# Esquematico_LEDS_16x16.net
KiCad netlist of a schematic drawn in Altium Designer
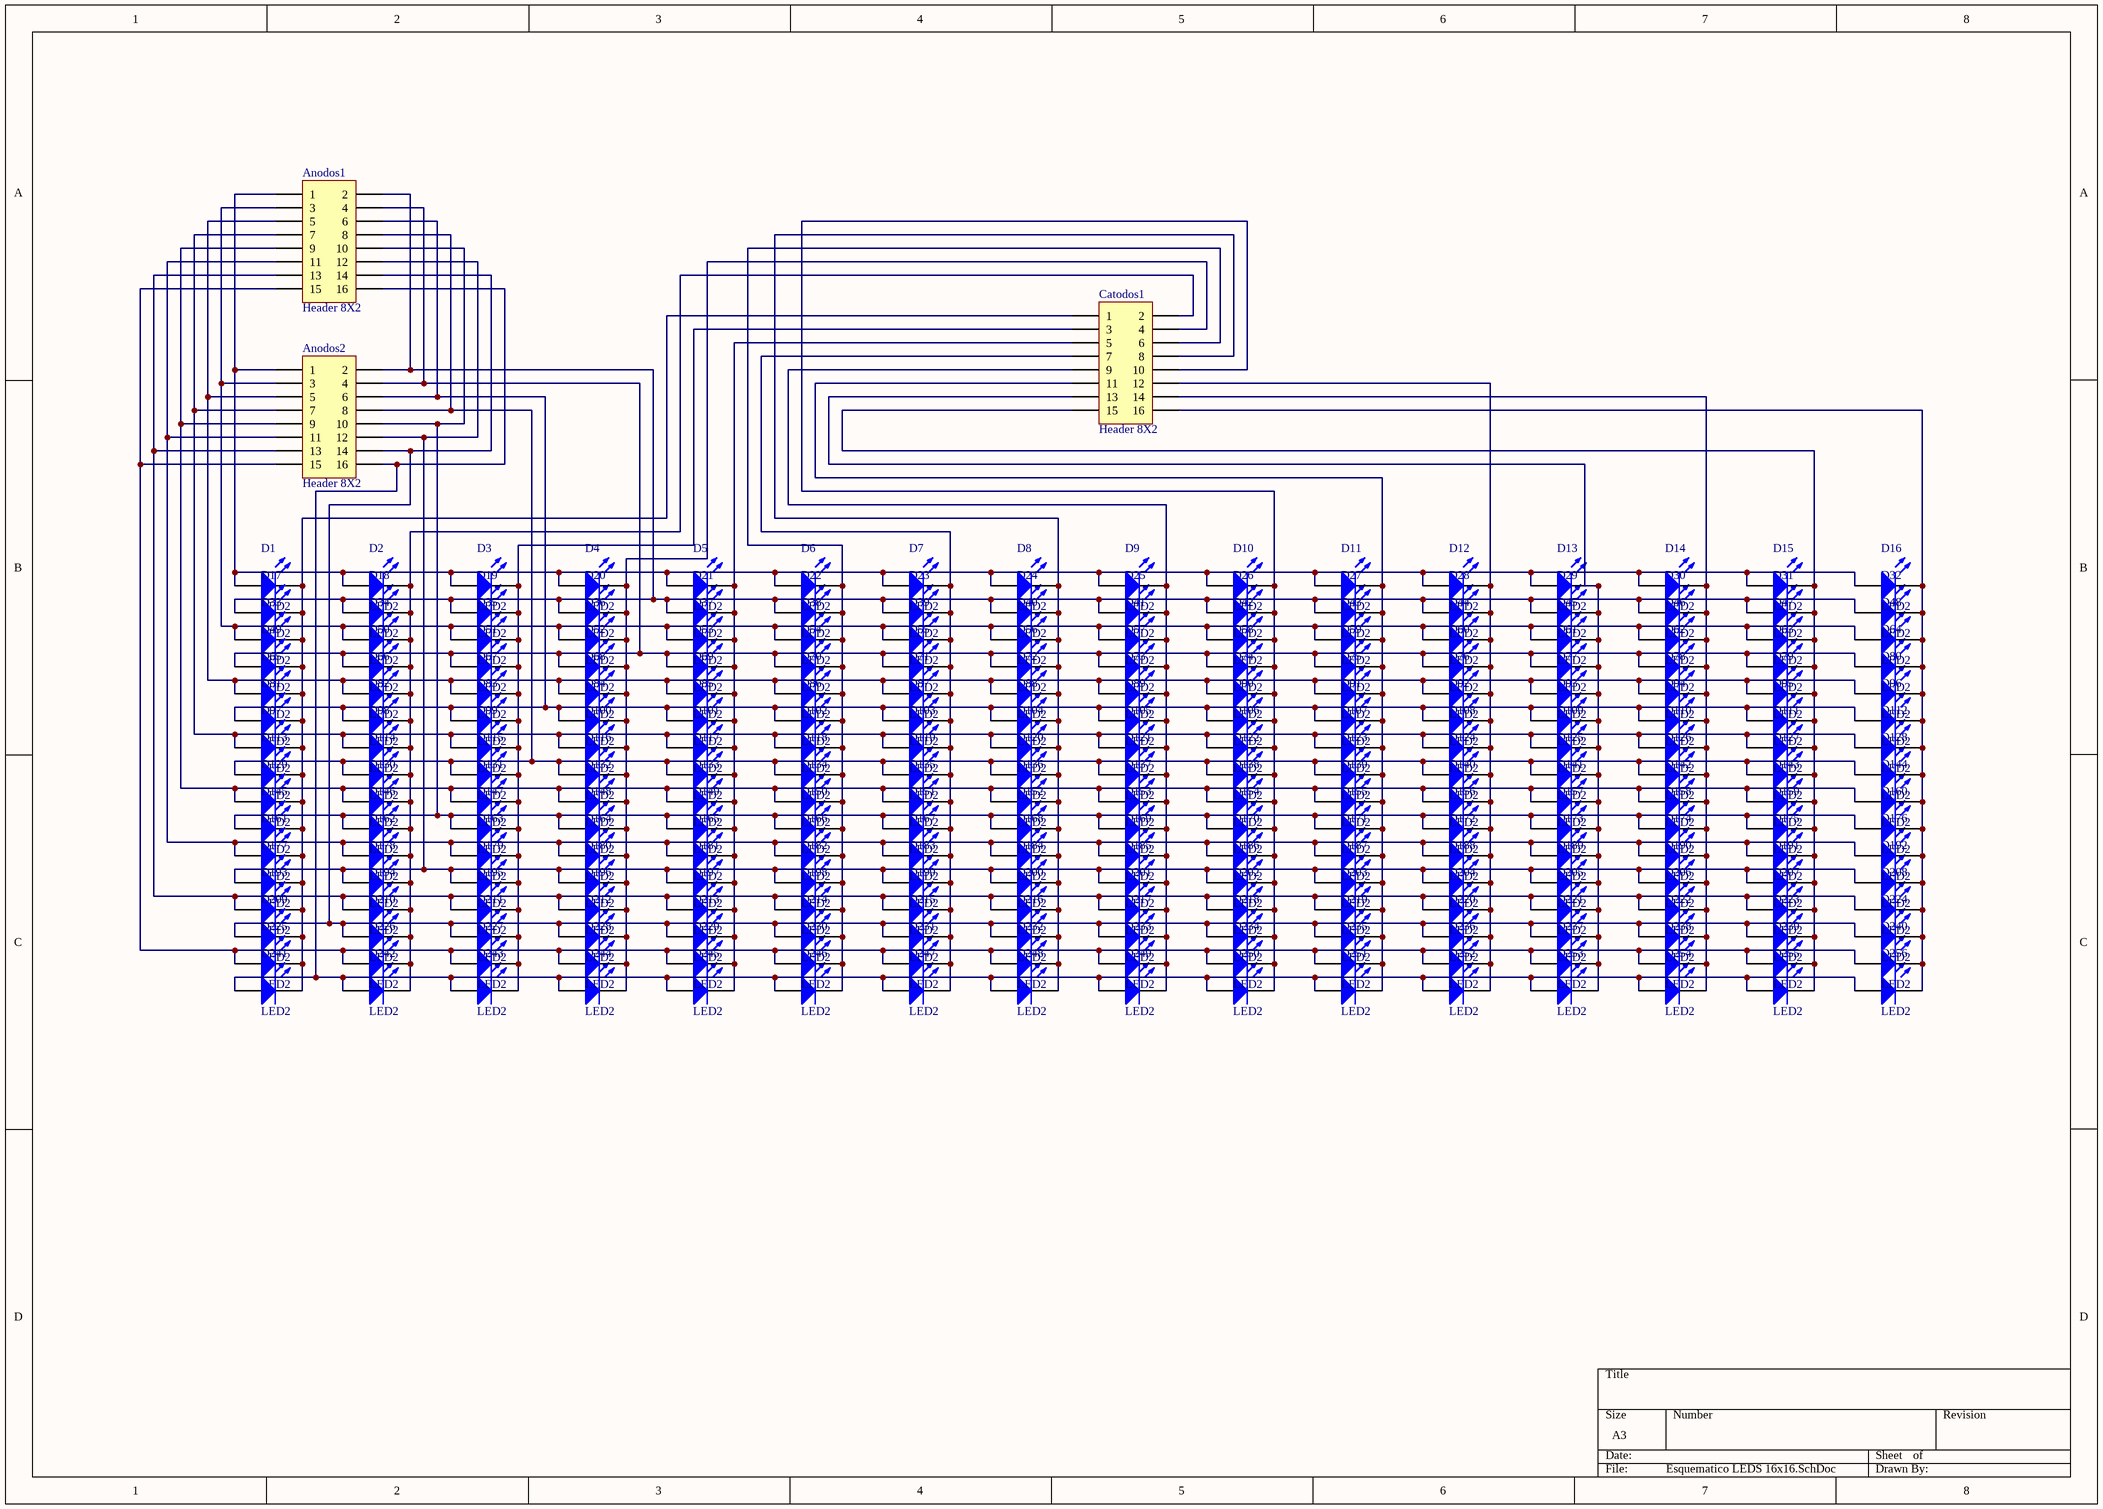
[diagram p0: Esquematico LEDS 16x16.SchDoc]

(export (version "E")
  (design (tool "Eeschema 10.0.6"))
  (components
    (comp (ref "Anodos1")
      (value "Header 8X2")
      (footprint "HDR2X8")
      (description "Header, 8-Pin, Dual row")
      (fields (field (name "PUBLISHER") "Altium Limited"))
      (libsource (lib "Miscellaneous Connectors") (part "Header 8X2"))
    )
    (comp (ref "Anodos2")
      (value "Header 8X2")
      (footprint "HDR2X8")
      (description "Header, 8-Pin, Dual row")
      (fields (field (name "PUBLISHER") "Altium Limited"))
      (libsource (lib "Miscellaneous Connectors") (part "Header 8X2"))
    )
    (comp (ref "Catodos1")
      (value "Header 8X2")
      (footprint "HDR2X8")
      (description "Header, 8-Pin, Dual row")
      (fields (field (name "PUBLISHER") "Altium Limited"))
      (libsource (lib "Miscellaneous Connectors") (part "Header 8X2"))
    )
    (comp (ref "D1")
      (value "LED2")
      (footprint "3.2X1.6X1.1")
      (description "Typical RED, GREEN, YELLOW, AMBER GaAs LED")
      (fields (field (name "PUBLISHER") "Altium Limited"))
      (libsource (lib "Miscellaneous Devices") (part "LED2"))
    )
    (comp (ref "D2")
      (value "LED2")
      (footprint "3.2X1.6X1.1")
      (description "Typical RED, GREEN, YELLOW, AMBER GaAs LED")
      (fields (field (name "PUBLISHER") "Altium Limited"))
      (libsource (lib "Miscellaneous Devices") (part "LED2"))
    )
    (comp (ref "D3")
      (value "LED2")
      (footprint "3.2X1.6X1.1")
      (description "Typical RED, GREEN, YELLOW, AMBER GaAs LED")
      (fields (field (name "PUBLISHER") "Altium Limited"))
      (libsource (lib "Miscellaneous Devices") (part "LED2"))
    )
    (comp (ref "D4")
      (value "LED2")
      (footprint "3.2X1.6X1.1")
      (description "Typical RED, GREEN, YELLOW, AMBER GaAs LED")
      (fields (field (name "PUBLISHER") "Altium Limited"))
      (libsource (lib "Miscellaneous Devices") (part "LED2"))
    )
    (comp (ref "D5")
      (value "LED2")
      (footprint "3.2X1.6X1.1")
      (description "Typical RED, GREEN, YELLOW, AMBER GaAs LED")
      (fields (field (name "PUBLISHER") "Altium Limited"))
      (libsource (lib "Miscellaneous Devices") (part "LED2"))
    )
    (comp (ref "D6")
      (value "LED2")
      (footprint "3.2X1.6X1.1")
      (description "Typical RED, GREEN, YELLOW, AMBER GaAs LED")
      (fields (field (name "PUBLISHER") "Altium Limited"))
      (libsource (lib "Miscellaneous Devices") (part "LED2"))
    )
    (comp (ref "D7")
      (value "LED2")
      (footprint "3.2X1.6X1.1")
      (description "Typical RED, GREEN, YELLOW, AMBER GaAs LED")
      (fields (field (name "PUBLISHER") "Altium Limited"))
      (libsource (lib "Miscellaneous Devices") (part "LED2"))
    )
    (comp (ref "D8")
      (value "LED2")
      (footprint "3.2X1.6X1.1")
      (description "Typical RED, GREEN, YELLOW, AMBER GaAs LED")
      (fields (field (name "PUBLISHER") "Altium Limited"))
      (libsource (lib "Miscellaneous Devices") (part "LED2"))
    )
    (comp (ref "D9")
      (value "LED2")
      (footprint "3.2X1.6X1.1")
      (description "Typical RED, GREEN, YELLOW, AMBER GaAs LED")
      (fields (field (name "PUBLISHER") "Altium Limited"))
      (libsource (lib "Miscellaneous Devices") (part "LED2"))
    )
    (comp (ref "D10")
      (value "LED2")
      (footprint "3.2X1.6X1.1")
      (description "Typical RED, GREEN, YELLOW, AMBER GaAs LED")
      (fields (field (name "PUBLISHER") "Altium Limited"))
      (libsource (lib "Miscellaneous Devices") (part "LED2"))
    )
    (comp (ref "D11")
      (value "LED2")
      (footprint "3.2X1.6X1.1")
      (description "Typical RED, GREEN, YELLOW, AMBER GaAs LED")
      (fields (field (name "PUBLISHER") "Altium Limited"))
      (libsource (lib "Miscellaneous Devices") (part "LED2"))
    )
    (comp (ref "D12")
      (value "LED2")
      (footprint "3.2X1.6X1.1")
      (description "Typical RED, GREEN, YELLOW, AMBER GaAs LED")
      (fields (field (name "PUBLISHER") "Altium Limited"))
      (libsource (lib "Miscellaneous Devices") (part "LED2"))
    )
    (comp (ref "D13")
      (value "LED2")
      (footprint "3.2X1.6X1.1")
      (description "Typical RED, GREEN, YELLOW, AMBER GaAs LED")
      (fields (field (name "PUBLISHER") "Altium Limited"))
      (libsource (lib "Miscellaneous Devices") (part "LED2"))
    )
    (comp (ref "D14")
      (value "LED2")
      (footprint "3.2X1.6X1.1")
      (description "Typical RED, GREEN, YELLOW, AMBER GaAs LED")
      (fields (field (name "PUBLISHER") "Altium Limited"))
      (libsource (lib "Miscellaneous Devices") (part "LED2"))
    )
    (comp (ref "D15")
      (value "LED2")
      (footprint "3.2X1.6X1.1")
      (description "Typical RED, GREEN, YELLOW, AMBER GaAs LED")
      (fields (field (name "PUBLISHER") "Altium Limited"))
      (libsource (lib "Miscellaneous Devices") (part "LED2"))
    )
    (comp (ref "D16")
      (value "LED2")
      (footprint "3.2X1.6X1.1")
      (description "Typical RED, GREEN, YELLOW, AMBER GaAs LED")
      (fields (field (name "PUBLISHER") "Altium Limited"))
      (libsource (lib "Miscellaneous Devices") (part "LED2"))
    )
    (comp (ref "D17")
      (value "LED2")
      (footprint "3.2X1.6X1.1")
      (description "Typical RED, GREEN, YELLOW, AMBER GaAs LED")
      (fields (field (name "PUBLISHER") "Altium Limited"))
      (libsource (lib "Miscellaneous Devices") (part "LED2"))
    )
    (comp (ref "D18")
      (value "LED2")
      (footprint "3.2X1.6X1.1")
      (description "Typical RED, GREEN, YELLOW, AMBER GaAs LED")
      (fields (field (name "PUBLISHER") "Altium Limited"))
      (libsource (lib "Miscellaneous Devices") (part "LED2"))
    )
    (comp (ref "D19")
      (value "LED2")
      (footprint "3.2X1.6X1.1")
      (description "Typical RED, GREEN, YELLOW, AMBER GaAs LED")
      (fields (field (name "PUBLISHER") "Altium Limited"))
      (libsource (lib "Miscellaneous Devices") (part "LED2"))
    )
    (comp (ref "D20")
      (value "LED2")
      (footprint "3.2X1.6X1.1")
      (description "Typical RED, GREEN, YELLOW, AMBER GaAs LED")
      (fields (field (name "PUBLISHER") "Altium Limited"))
      (libsource (lib "Miscellaneous Devices") (part "LED2"))
    )
    (comp (ref "D21")
      (value "LED2")
      (footprint "3.2X1.6X1.1")
      (description "Typical RED, GREEN, YELLOW, AMBER GaAs LED")
      (fields (field (name "PUBLISHER") "Altium Limited"))
      (libsource (lib "Miscellaneous Devices") (part "LED2"))
    )
    (comp (ref "D22")
      (value "LED2")
      (footprint "3.2X1.6X1.1")
      (description "Typical RED, GREEN, YELLOW, AMBER GaAs LED")
      (fields (field (name "PUBLISHER") "Altium Limited"))
      (libsource (lib "Miscellaneous Devices") (part "LED2"))
    )
    (comp (ref "D23")
      (value "LED2")
      (footprint "3.2X1.6X1.1")
      (description "Typical RED, GREEN, YELLOW, AMBER GaAs LED")
      (fields (field (name "PUBLISHER") "Altium Limited"))
      (libsource (lib "Miscellaneous Devices") (part "LED2"))
    )
    (comp (ref "D24")
      (value "LED2")
      (footprint "3.2X1.6X1.1")
      (description "Typical RED, GREEN, YELLOW, AMBER GaAs LED")
      (fields (field (name "PUBLISHER") "Altium Limited"))
      (libsource (lib "Miscellaneous Devices") (part "LED2"))
    )
    (comp (ref "D25")
      (value "LED2")
      (footprint "3.2X1.6X1.1")
      (description "Typical RED, GREEN, YELLOW, AMBER GaAs LED")
      (fields (field (name "PUBLISHER") "Altium Limited"))
      (libsource (lib "Miscellaneous Devices") (part "LED2"))
    )
    (comp (ref "D26")
      (value "LED2")
      (footprint "3.2X1.6X1.1")
      (description "Typical RED, GREEN, YELLOW, AMBER GaAs LED")
      (fields (field (name "PUBLISHER") "Altium Limited"))
      (libsource (lib "Miscellaneous Devices") (part "LED2"))
    )
    (comp (ref "D27")
      (value "LED2")
      (footprint "3.2X1.6X1.1")
      (description "Typical RED, GREEN, YELLOW, AMBER GaAs LED")
      (fields (field (name "PUBLISHER") "Altium Limited"))
      (libsource (lib "Miscellaneous Devices") (part "LED2"))
    )
    (comp (ref "D28")
      (value "LED2")
      (footprint "3.2X1.6X1.1")
      (description "Typical RED, GREEN, YELLOW, AMBER GaAs LED")
      (fields (field (name "PUBLISHER") "Altium Limited"))
      (libsource (lib "Miscellaneous Devices") (part "LED2"))
    )
    (comp (ref "D29")
      (value "LED2")
      (footprint "3.2X1.6X1.1")
      (description "Typical RED, GREEN, YELLOW, AMBER GaAs LED")
      (fields (field (name "PUBLISHER") "Altium Limited"))
      (libsource (lib "Miscellaneous Devices") (part "LED2"))
    )
    (comp (ref "D30")
      (value "LED2")
      (footprint "3.2X1.6X1.1")
      (description "Typical RED, GREEN, YELLOW, AMBER GaAs LED")
      (fields (field (name "PUBLISHER") "Altium Limited"))
      (libsource (lib "Miscellaneous Devices") (part "LED2"))
    )
    (comp (ref "D31")
      (value "LED2")
      (footprint "3.2X1.6X1.1")
      (description "Typical RED, GREEN, YELLOW, AMBER GaAs LED")
      (fields (field (name "PUBLISHER") "Altium Limited"))
      (libsource (lib "Miscellaneous Devices") (part "LED2"))
    )
    (comp (ref "D32")
      (value "LED2")
      (footprint "3.2X1.6X1.1")
      (description "Typical RED, GREEN, YELLOW, AMBER GaAs LED")
      (fields (field (name "PUBLISHER") "Altium Limited"))
      (libsource (lib "Miscellaneous Devices") (part "LED2"))
    )
    (comp (ref "D33")
      (value "LED2")
      (footprint "3.2X1.6X1.1")
      (description "Typical RED, GREEN, YELLOW, AMBER GaAs LED")
      (fields (field (name "PUBLISHER") "Altium Limited"))
      (libsource (lib "Miscellaneous Devices") (part "LED2"))
    )
    (comp (ref "D34")
      (value "LED2")
      (footprint "3.2X1.6X1.1")
      (description "Typical RED, GREEN, YELLOW, AMBER GaAs LED")
      (fields (field (name "PUBLISHER") "Altium Limited"))
      (libsource (lib "Miscellaneous Devices") (part "LED2"))
    )
    (comp (ref "D35")
      (value "LED2")
      (footprint "3.2X1.6X1.1")
      (description "Typical RED, GREEN, YELLOW, AMBER GaAs LED")
      (fields (field (name "PUBLISHER") "Altium Limited"))
      (libsource (lib "Miscellaneous Devices") (part "LED2"))
    )
    (comp (ref "D36")
      (value "LED2")
      (footprint "3.2X1.6X1.1")
      (description "Typical RED, GREEN, YELLOW, AMBER GaAs LED")
      (fields (field (name "PUBLISHER") "Altium Limited"))
      (libsource (lib "Miscellaneous Devices") (part "LED2"))
    )
    (comp (ref "D37")
      (value "LED2")
      (footprint "3.2X1.6X1.1")
      (description "Typical RED, GREEN, YELLOW, AMBER GaAs LED")
      (fields (field (name "PUBLISHER") "Altium Limited"))
      (libsource (lib "Miscellaneous Devices") (part "LED2"))
    )
    (comp (ref "D38")
      (value "LED2")
      (footprint "3.2X1.6X1.1")
      (description "Typical RED, GREEN, YELLOW, AMBER GaAs LED")
      (fields (field (name "PUBLISHER") "Altium Limited"))
      (libsource (lib "Miscellaneous Devices") (part "LED2"))
    )
    (comp (ref "D39")
      (value "LED2")
      (footprint "3.2X1.6X1.1")
      (description "Typical RED, GREEN, YELLOW, AMBER GaAs LED")
      (fields (field (name "PUBLISHER") "Altium Limited"))
      (libsource (lib "Miscellaneous Devices") (part "LED2"))
    )
    (comp (ref "D40")
      (value "LED2")
      (footprint "3.2X1.6X1.1")
      (description "Typical RED, GREEN, YELLOW, AMBER GaAs LED")
      (fields (field (name "PUBLISHER") "Altium Limited"))
      (libsource (lib "Miscellaneous Devices") (part "LED2"))
    )
    (comp (ref "D41")
      (value "LED2")
      (footprint "3.2X1.6X1.1")
      (description "Typical RED, GREEN, YELLOW, AMBER GaAs LED")
      (fields (field (name "PUBLISHER") "Altium Limited"))
      (libsource (lib "Miscellaneous Devices") (part "LED2"))
    )
    (comp (ref "D42")
      (value "LED2")
      (footprint "3.2X1.6X1.1")
      (description "Typical RED, GREEN, YELLOW, AMBER GaAs LED")
      (fields (field (name "PUBLISHER") "Altium Limited"))
      (libsource (lib "Miscellaneous Devices") (part "LED2"))
    )
    (comp (ref "D43")
      (value "LED2")
      (footprint "3.2X1.6X1.1")
      (description "Typical RED, GREEN, YELLOW, AMBER GaAs LED")
      (fields (field (name "PUBLISHER") "Altium Limited"))
      (libsource (lib "Miscellaneous Devices") (part "LED2"))
    )
    (comp (ref "D44")
      (value "LED2")
      (footprint "3.2X1.6X1.1")
      (description "Typical RED, GREEN, YELLOW, AMBER GaAs LED")
      (fields (field (name "PUBLISHER") "Altium Limited"))
      (libsource (lib "Miscellaneous Devices") (part "LED2"))
    )
    (comp (ref "D45")
      (value "LED2")
      (footprint "3.2X1.6X1.1")
      (description "Typical RED, GREEN, YELLOW, AMBER GaAs LED")
      (fields (field (name "PUBLISHER") "Altium Limited"))
      (libsource (lib "Miscellaneous Devices") (part "LED2"))
    )
    (comp (ref "D46")
      (value "LED2")
      (footprint "3.2X1.6X1.1")
      (description "Typical RED, GREEN, YELLOW, AMBER GaAs LED")
      (fields (field (name "PUBLISHER") "Altium Limited"))
      (libsource (lib "Miscellaneous Devices") (part "LED2"))
    )
    (comp (ref "D47")
      (value "LED2")
      (footprint "3.2X1.6X1.1")
      (description "Typical RED, GREEN, YELLOW, AMBER GaAs LED")
      (fields (field (name "PUBLISHER") "Altium Limited"))
      (libsource (lib "Miscellaneous Devices") (part "LED2"))
    )
    (comp (ref "D48")
      (value "LED2")
      (footprint "3.2X1.6X1.1")
      (description "Typical RED, GREEN, YELLOW, AMBER GaAs LED")
      (fields (field (name "PUBLISHER") "Altium Limited"))
      (libsource (lib "Miscellaneous Devices") (part "LED2"))
    )
    (comp (ref "D49")
      (value "LED2")
      (footprint "3.2X1.6X1.1")
      (description "Typical RED, GREEN, YELLOW, AMBER GaAs LED")
      (fields (field (name "PUBLISHER") "Altium Limited"))
      (libsource (lib "Miscellaneous Devices") (part "LED2"))
    )
    (comp (ref "D50")
      (value "LED2")
      (footprint "3.2X1.6X1.1")
      (description "Typical RED, GREEN, YELLOW, AMBER GaAs LED")
      (fields (field (name "PUBLISHER") "Altium Limited"))
      (libsource (lib "Miscellaneous Devices") (part "LED2"))
    )
    (comp (ref "D51")
      (value "LED2")
      (footprint "3.2X1.6X1.1")
      (description "Typical RED, GREEN, YELLOW, AMBER GaAs LED")
      (fields (field (name "PUBLISHER") "Altium Limited"))
      (libsource (lib "Miscellaneous Devices") (part "LED2"))
    )
    (comp (ref "D52")
      (value "LED2")
      (footprint "3.2X1.6X1.1")
      (description "Typical RED, GREEN, YELLOW, AMBER GaAs LED")
      (fields (field (name "PUBLISHER") "Altium Limited"))
      (libsource (lib "Miscellaneous Devices") (part "LED2"))
    )
    (comp (ref "D53")
      (value "LED2")
      (footprint "3.2X1.6X1.1")
      (description "Typical RED, GREEN, YELLOW, AMBER GaAs LED")
      (fields (field (name "PUBLISHER") "Altium Limited"))
      (libsource (lib "Miscellaneous Devices") (part "LED2"))
    )
    (comp (ref "D54")
      (value "LED2")
      (footprint "3.2X1.6X1.1")
      (description "Typical RED, GREEN, YELLOW, AMBER GaAs LED")
      (fields (field (name "PUBLISHER") "Altium Limited"))
      (libsource (lib "Miscellaneous Devices") (part "LED2"))
    )
    (comp (ref "D55")
      (value "LED2")
      (footprint "3.2X1.6X1.1")
      (description "Typical RED, GREEN, YELLOW, AMBER GaAs LED")
      (fields (field (name "PUBLISHER") "Altium Limited"))
      (libsource (lib "Miscellaneous Devices") (part "LED2"))
    )
    (comp (ref "D56")
      (value "LED2")
      (footprint "3.2X1.6X1.1")
      (description "Typical RED, GREEN, YELLOW, AMBER GaAs LED")
      (fields (field (name "PUBLISHER") "Altium Limited"))
      (libsource (lib "Miscellaneous Devices") (part "LED2"))
    )
    (comp (ref "D57")
      (value "LED2")
      (footprint "3.2X1.6X1.1")
      (description "Typical RED, GREEN, YELLOW, AMBER GaAs LED")
      (fields (field (name "PUBLISHER") "Altium Limited"))
      (libsource (lib "Miscellaneous Devices") (part "LED2"))
    )
    (comp (ref "D58")
      (value "LED2")
      (footprint "3.2X1.6X1.1")
      (description "Typical RED, GREEN, YELLOW, AMBER GaAs LED")
      (fields (field (name "PUBLISHER") "Altium Limited"))
      (libsource (lib "Miscellaneous Devices") (part "LED2"))
    )
    (comp (ref "D59")
      (value "LED2")
      (footprint "3.2X1.6X1.1")
      (description "Typical RED, GREEN, YELLOW, AMBER GaAs LED")
      (fields (field (name "PUBLISHER") "Altium Limited"))
      (libsource (lib "Miscellaneous Devices") (part "LED2"))
    )
    (comp (ref "D60")
      (value "LED2")
      (footprint "3.2X1.6X1.1")
      (description "Typical RED, GREEN, YELLOW, AMBER GaAs LED")
      (fields (field (name "PUBLISHER") "Altium Limited"))
      (libsource (lib "Miscellaneous Devices") (part "LED2"))
    )
    (comp (ref "D61")
      (value "LED2")
      (footprint "3.2X1.6X1.1")
      (description "Typical RED, GREEN, YELLOW, AMBER GaAs LED")
      (fields (field (name "PUBLISHER") "Altium Limited"))
      (libsource (lib "Miscellaneous Devices") (part "LED2"))
    )
    (comp (ref "D62")
      (value "LED2")
      (footprint "3.2X1.6X1.1")
      (description "Typical RED, GREEN, YELLOW, AMBER GaAs LED")
      (fields (field (name "PUBLISHER") "Altium Limited"))
      (libsource (lib "Miscellaneous Devices") (part "LED2"))
    )
    (comp (ref "D63")
      (value "LED2")
      (footprint "3.2X1.6X1.1")
      (description "Typical RED, GREEN, YELLOW, AMBER GaAs LED")
      (fields (field (name "PUBLISHER") "Altium Limited"))
      (libsource (lib "Miscellaneous Devices") (part "LED2"))
    )
    (comp (ref "D64")
      (value "LED2")
      (footprint "3.2X1.6X1.1")
      (description "Typical RED, GREEN, YELLOW, AMBER GaAs LED")
      (fields (field (name "PUBLISHER") "Altium Limited"))
      (libsource (lib "Miscellaneous Devices") (part "LED2"))
    )
    (comp (ref "D65")
      (value "LED2")
      (footprint "3.2X1.6X1.1")
      (description "Typical RED, GREEN, YELLOW, AMBER GaAs LED")
      (fields (field (name "PUBLISHER") "Altium Limited"))
      (libsource (lib "Miscellaneous Devices") (part "LED2"))
    )
    (comp (ref "D66")
      (value "LED2")
      (footprint "3.2X1.6X1.1")
      (description "Typical RED, GREEN, YELLOW, AMBER GaAs LED")
      (fields (field (name "PUBLISHER") "Altium Limited"))
      (libsource (lib "Miscellaneous Devices") (part "LED2"))
    )
    (comp (ref "D67")
      (value "LED2")
      (footprint "3.2X1.6X1.1")
      (description "Typical RED, GREEN, YELLOW, AMBER GaAs LED")
      (fields (field (name "PUBLISHER") "Altium Limited"))
      (libsource (lib "Miscellaneous Devices") (part "LED2"))
    )
    (comp (ref "D68")
      (value "LED2")
      (footprint "3.2X1.6X1.1")
      (description "Typical RED, GREEN, YELLOW, AMBER GaAs LED")
      (fields (field (name "PUBLISHER") "Altium Limited"))
      (libsource (lib "Miscellaneous Devices") (part "LED2"))
    )
    (comp (ref "D69")
      (value "LED2")
      (footprint "3.2X1.6X1.1")
      (description "Typical RED, GREEN, YELLOW, AMBER GaAs LED")
      (fields (field (name "PUBLISHER") "Altium Limited"))
      (libsource (lib "Miscellaneous Devices") (part "LED2"))
    )
    (comp (ref "D70")
      (value "LED2")
      (footprint "3.2X1.6X1.1")
      (description "Typical RED, GREEN, YELLOW, AMBER GaAs LED")
      (fields (field (name "PUBLISHER") "Altium Limited"))
      (libsource (lib "Miscellaneous Devices") (part "LED2"))
    )
    (comp (ref "D71")
      (value "LED2")
      (footprint "3.2X1.6X1.1")
      (description "Typical RED, GREEN, YELLOW, AMBER GaAs LED")
      (fields (field (name "PUBLISHER") "Altium Limited"))
      (libsource (lib "Miscellaneous Devices") (part "LED2"))
    )
    (comp (ref "D72")
      (value "LED2")
      (footprint "3.2X1.6X1.1")
      (description "Typical RED, GREEN, YELLOW, AMBER GaAs LED")
      (fields (field (name "PUBLISHER") "Altium Limited"))
      (libsource (lib "Miscellaneous Devices") (part "LED2"))
    )
    (comp (ref "D73")
      (value "LED2")
      (footprint "3.2X1.6X1.1")
      (description "Typical RED, GREEN, YELLOW, AMBER GaAs LED")
      (fields (field (name "PUBLISHER") "Altium Limited"))
      (libsource (lib "Miscellaneous Devices") (part "LED2"))
    )
    (comp (ref "D74")
      (value "LED2")
      (footprint "3.2X1.6X1.1")
      (description "Typical RED, GREEN, YELLOW, AMBER GaAs LED")
      (fields (field (name "PUBLISHER") "Altium Limited"))
      (libsource (lib "Miscellaneous Devices") (part "LED2"))
    )
    (comp (ref "D75")
      (value "LED2")
      (footprint "3.2X1.6X1.1")
      (description "Typical RED, GREEN, YELLOW, AMBER GaAs LED")
      (fields (field (name "PUBLISHER") "Altium Limited"))
      (libsource (lib "Miscellaneous Devices") (part "LED2"))
    )
    (comp (ref "D76")
      (value "LED2")
      (footprint "3.2X1.6X1.1")
      (description "Typical RED, GREEN, YELLOW, AMBER GaAs LED")
      (fields (field (name "PUBLISHER") "Altium Limited"))
      (libsource (lib "Miscellaneous Devices") (part "LED2"))
    )
    (comp (ref "D77")
      (value "LED2")
      (footprint "3.2X1.6X1.1")
      (description "Typical RED, GREEN, YELLOW, AMBER GaAs LED")
      (fields (field (name "PUBLISHER") "Altium Limited"))
      (libsource (lib "Miscellaneous Devices") (part "LED2"))
    )
    (comp (ref "D78")
      (value "LED2")
      (footprint "3.2X1.6X1.1")
      (description "Typical RED, GREEN, YELLOW, AMBER GaAs LED")
      (fields (field (name "PUBLISHER") "Altium Limited"))
      (libsource (lib "Miscellaneous Devices") (part "LED2"))
    )
    (comp (ref "D79")
      (value "LED2")
      (footprint "3.2X1.6X1.1")
      (description "Typical RED, GREEN, YELLOW, AMBER GaAs LED")
      (fields (field (name "PUBLISHER") "Altium Limited"))
      (libsource (lib "Miscellaneous Devices") (part "LED2"))
    )
    (comp (ref "D80")
      (value "LED2")
      (footprint "3.2X1.6X1.1")
      (description "Typical RED, GREEN, YELLOW, AMBER GaAs LED")
      (fields (field (name "PUBLISHER") "Altium Limited"))
      (libsource (lib "Miscellaneous Devices") (part "LED2"))
    )
    (comp (ref "D81")
      (value "LED2")
      (footprint "3.2X1.6X1.1")
      (description "Typical RED, GREEN, YELLOW, AMBER GaAs LED")
      (fields (field (name "PUBLISHER") "Altium Limited"))
      (libsource (lib "Miscellaneous Devices") (part "LED2"))
    )
    (comp (ref "D82")
      (value "LED2")
      (footprint "3.2X1.6X1.1")
      (description "Typical RED, GREEN, YELLOW, AMBER GaAs LED")
      (fields (field (name "PUBLISHER") "Altium Limited"))
      (libsource (lib "Miscellaneous Devices") (part "LED2"))
    )
    (comp (ref "D83")
      (value "LED2")
      (footprint "3.2X1.6X1.1")
      (description "Typical RED, GREEN, YELLOW, AMBER GaAs LED")
      (fields (field (name "PUBLISHER") "Altium Limited"))
      (libsource (lib "Miscellaneous Devices") (part "LED2"))
    )
    (comp (ref "D84")
      (value "LED2")
      (footprint "3.2X1.6X1.1")
      (description "Typical RED, GREEN, YELLOW, AMBER GaAs LED")
      (fields (field (name "PUBLISHER") "Altium Limited"))
      (libsource (lib "Miscellaneous Devices") (part "LED2"))
    )
    (comp (ref "D85")
      (value "LED2")
      (footprint "3.2X1.6X1.1")
      (description "Typical RED, GREEN, YELLOW, AMBER GaAs LED")
      (fields (field (name "PUBLISHER") "Altium Limited"))
      (libsource (lib "Miscellaneous Devices") (part "LED2"))
    )
    (comp (ref "D86")
      (value "LED2")
      (footprint "3.2X1.6X1.1")
      (description "Typical RED, GREEN, YELLOW, AMBER GaAs LED")
      (fields (field (name "PUBLISHER") "Altium Limited"))
      (libsource (lib "Miscellaneous Devices") (part "LED2"))
    )
    (comp (ref "D87")
      (value "LED2")
      (footprint "3.2X1.6X1.1")
      (description "Typical RED, GREEN, YELLOW, AMBER GaAs LED")
      (fields (field (name "PUBLISHER") "Altium Limited"))
      (libsource (lib "Miscellaneous Devices") (part "LED2"))
    )
    (comp (ref "D88")
      (value "LED2")
      (footprint "3.2X1.6X1.1")
      (description "Typical RED, GREEN, YELLOW, AMBER GaAs LED")
      (fields (field (name "PUBLISHER") "Altium Limited"))
      (libsource (lib "Miscellaneous Devices") (part "LED2"))
    )
    (comp (ref "D89")
      (value "LED2")
      (footprint "3.2X1.6X1.1")
      (description "Typical RED, GREEN, YELLOW, AMBER GaAs LED")
      (fields (field (name "PUBLISHER") "Altium Limited"))
      (libsource (lib "Miscellaneous Devices") (part "LED2"))
    )
    (comp (ref "D90")
      (value "LED2")
      (footprint "3.2X1.6X1.1")
      (description "Typical RED, GREEN, YELLOW, AMBER GaAs LED")
      (fields (field (name "PUBLISHER") "Altium Limited"))
      (libsource (lib "Miscellaneous Devices") (part "LED2"))
    )
    (comp (ref "D91")
      (value "LED2")
      (footprint "3.2X1.6X1.1")
      (description "Typical RED, GREEN, YELLOW, AMBER GaAs LED")
      (fields (field (name "PUBLISHER") "Altium Limited"))
      (libsource (lib "Miscellaneous Devices") (part "LED2"))
    )
    (comp (ref "D92")
      (value "LED2")
      (footprint "3.2X1.6X1.1")
      (description "Typical RED, GREEN, YELLOW, AMBER GaAs LED")
      (fields (field (name "PUBLISHER") "Altium Limited"))
      (libsource (lib "Miscellaneous Devices") (part "LED2"))
    )
    (comp (ref "D93")
      (value "LED2")
      (footprint "3.2X1.6X1.1")
      (description "Typical RED, GREEN, YELLOW, AMBER GaAs LED")
      (fields (field (name "PUBLISHER") "Altium Limited"))
      (libsource (lib "Miscellaneous Devices") (part "LED2"))
    )
    (comp (ref "D94")
      (value "LED2")
      (footprint "3.2X1.6X1.1")
      (description "Typical RED, GREEN, YELLOW, AMBER GaAs LED")
      (fields (field (name "PUBLISHER") "Altium Limited"))
      (libsource (lib "Miscellaneous Devices") (part "LED2"))
    )
    (comp (ref "D95")
      (value "LED2")
      (footprint "3.2X1.6X1.1")
      (description "Typical RED, GREEN, YELLOW, AMBER GaAs LED")
      (fields (field (name "PUBLISHER") "Altium Limited"))
      (libsource (lib "Miscellaneous Devices") (part "LED2"))
    )
    (comp (ref "D96")
      (value "LED2")
      (footprint "3.2X1.6X1.1")
      (description "Typical RED, GREEN, YELLOW, AMBER GaAs LED")
      (fields (field (name "PUBLISHER") "Altium Limited"))
      (libsource (lib "Miscellaneous Devices") (part "LED2"))
    )
    (comp (ref "D97")
      (value "LED2")
      (footprint "3.2X1.6X1.1")
      (description "Typical RED, GREEN, YELLOW, AMBER GaAs LED")
      (fields (field (name "PUBLISHER") "Altium Limited"))
      (libsource (lib "Miscellaneous Devices") (part "LED2"))
    )
    (comp (ref "D98")
      (value "LED2")
      (footprint "3.2X1.6X1.1")
      (description "Typical RED, GREEN, YELLOW, AMBER GaAs LED")
      (fields (field (name "PUBLISHER") "Altium Limited"))
      (libsource (lib "Miscellaneous Devices") (part "LED2"))
    )
    (comp (ref "D99")
      (value "LED2")
      (footprint "3.2X1.6X1.1")
      (description "Typical RED, GREEN, YELLOW, AMBER GaAs LED")
      (fields (field (name "PUBLISHER") "Altium Limited"))
      (libsource (lib "Miscellaneous Devices") (part "LED2"))
    )
    (comp (ref "D100")
      (value "LED2")
      (footprint "3.2X1.6X1.1")
      (description "Typical RED, GREEN, YELLOW, AMBER GaAs LED")
      (fields (field (name "PUBLISHER") "Altium Limited"))
      (libsource (lib "Miscellaneous Devices") (part "LED2"))
    )
    (comp (ref "D101")
      (value "LED2")
      (footprint "3.2X1.6X1.1")
      (description "Typical RED, GREEN, YELLOW, AMBER GaAs LED")
      (fields (field (name "PUBLISHER") "Altium Limited"))
      (libsource (lib "Miscellaneous Devices") (part "LED2"))
    )
    (comp (ref "D102")
      (value "LED2")
      (footprint "3.2X1.6X1.1")
      (description "Typical RED, GREEN, YELLOW, AMBER GaAs LED")
      (fields (field (name "PUBLISHER") "Altium Limited"))
      (libsource (lib "Miscellaneous Devices") (part "LED2"))
    )
    (comp (ref "D103")
      (value "LED2")
      (footprint "3.2X1.6X1.1")
      (description "Typical RED, GREEN, YELLOW, AMBER GaAs LED")
      (fields (field (name "PUBLISHER") "Altium Limited"))
      (libsource (lib "Miscellaneous Devices") (part "LED2"))
    )
    (comp (ref "D104")
      (value "LED2")
      (footprint "3.2X1.6X1.1")
      (description "Typical RED, GREEN, YELLOW, AMBER GaAs LED")
      (fields (field (name "PUBLISHER") "Altium Limited"))
      (libsource (lib "Miscellaneous Devices") (part "LED2"))
    )
    (comp (ref "D105")
      (value "LED2")
      (footprint "3.2X1.6X1.1")
      (description "Typical RED, GREEN, YELLOW, AMBER GaAs LED")
      (fields (field (name "PUBLISHER") "Altium Limited"))
      (libsource (lib "Miscellaneous Devices") (part "LED2"))
    )
    (comp (ref "D106")
      (value "LED2")
      (footprint "3.2X1.6X1.1")
      (description "Typical RED, GREEN, YELLOW, AMBER GaAs LED")
      (fields (field (name "PUBLISHER") "Altium Limited"))
      (libsource (lib "Miscellaneous Devices") (part "LED2"))
    )
    (comp (ref "D107")
      (value "LED2")
      (footprint "3.2X1.6X1.1")
      (description "Typical RED, GREEN, YELLOW, AMBER GaAs LED")
      (fields (field (name "PUBLISHER") "Altium Limited"))
      (libsource (lib "Miscellaneous Devices") (part "LED2"))
    )
    (comp (ref "D108")
      (value "LED2")
      (footprint "3.2X1.6X1.1")
      (description "Typical RED, GREEN, YELLOW, AMBER GaAs LED")
      (fields (field (name "PUBLISHER") "Altium Limited"))
      (libsource (lib "Miscellaneous Devices") (part "LED2"))
    )
    (comp (ref "D109")
      (value "LED2")
      (footprint "3.2X1.6X1.1")
      (description "Typical RED, GREEN, YELLOW, AMBER GaAs LED")
      (fields (field (name "PUBLISHER") "Altium Limited"))
      (libsource (lib "Miscellaneous Devices") (part "LED2"))
    )
    (comp (ref "D110")
      (value "LED2")
      (footprint "3.2X1.6X1.1")
      (description "Typical RED, GREEN, YELLOW, AMBER GaAs LED")
      (fields (field (name "PUBLISHER") "Altium Limited"))
      (libsource (lib "Miscellaneous Devices") (part "LED2"))
    )
    (comp (ref "D111")
      (value "LED2")
      (footprint "3.2X1.6X1.1")
      (description "Typical RED, GREEN, YELLOW, AMBER GaAs LED")
      (fields (field (name "PUBLISHER") "Altium Limited"))
      (libsource (lib "Miscellaneous Devices") (part "LED2"))
    )
    (comp (ref "D112")
      (value "LED2")
      (footprint "3.2X1.6X1.1")
      (description "Typical RED, GREEN, YELLOW, AMBER GaAs LED")
      (fields (field (name "PUBLISHER") "Altium Limited"))
      (libsource (lib "Miscellaneous Devices") (part "LED2"))
    )
    (comp (ref "D113")
      (value "LED2")
      (footprint "3.2X1.6X1.1")
      (description "Typical RED, GREEN, YELLOW, AMBER GaAs LED")
      (fields (field (name "PUBLISHER") "Altium Limited"))
      (libsource (lib "Miscellaneous Devices") (part "LED2"))
    )
    (comp (ref "D114")
      (value "LED2")
      (footprint "3.2X1.6X1.1")
      (description "Typical RED, GREEN, YELLOW, AMBER GaAs LED")
      (fields (field (name "PUBLISHER") "Altium Limited"))
      (libsource (lib "Miscellaneous Devices") (part "LED2"))
    )
    (comp (ref "D115")
      (value "LED2")
      (footprint "3.2X1.6X1.1")
      (description "Typical RED, GREEN, YELLOW, AMBER GaAs LED")
      (fields (field (name "PUBLISHER") "Altium Limited"))
      (libsource (lib "Miscellaneous Devices") (part "LED2"))
    )
    (comp (ref "D116")
      (value "LED2")
      (footprint "3.2X1.6X1.1")
      (description "Typical RED, GREEN, YELLOW, AMBER GaAs LED")
      (fields (field (name "PUBLISHER") "Altium Limited"))
      (libsource (lib "Miscellaneous Devices") (part "LED2"))
    )
    (comp (ref "D117")
      (value "LED2")
      (footprint "3.2X1.6X1.1")
      (description "Typical RED, GREEN, YELLOW, AMBER GaAs LED")
      (fields (field (name "PUBLISHER") "Altium Limited"))
      (libsource (lib "Miscellaneous Devices") (part "LED2"))
    )
    (comp (ref "D118")
      (value "LED2")
      (footprint "3.2X1.6X1.1")
      (description "Typical RED, GREEN, YELLOW, AMBER GaAs LED")
      (fields (field (name "PUBLISHER") "Altium Limited"))
      (libsource (lib "Miscellaneous Devices") (part "LED2"))
    )
    (comp (ref "D119")
      (value "LED2")
      (footprint "3.2X1.6X1.1")
      (description "Typical RED, GREEN, YELLOW, AMBER GaAs LED")
      (fields (field (name "PUBLISHER") "Altium Limited"))
      (libsource (lib "Miscellaneous Devices") (part "LED2"))
    )
    (comp (ref "D120")
      (value "LED2")
      (footprint "3.2X1.6X1.1")
      (description "Typical RED, GREEN, YELLOW, AMBER GaAs LED")
      (fields (field (name "PUBLISHER") "Altium Limited"))
      (libsource (lib "Miscellaneous Devices") (part "LED2"))
    )
    (comp (ref "D121")
      (value "LED2")
      (footprint "3.2X1.6X1.1")
      (description "Typical RED, GREEN, YELLOW, AMBER GaAs LED")
      (fields (field (name "PUBLISHER") "Altium Limited"))
      (libsource (lib "Miscellaneous Devices") (part "LED2"))
    )
    (comp (ref "D122")
      (value "LED2")
      (footprint "3.2X1.6X1.1")
      (description "Typical RED, GREEN, YELLOW, AMBER GaAs LED")
      (fields (field (name "PUBLISHER") "Altium Limited"))
      (libsource (lib "Miscellaneous Devices") (part "LED2"))
    )
    (comp (ref "D123")
      (value "LED2")
      (footprint "3.2X1.6X1.1")
      (description "Typical RED, GREEN, YELLOW, AMBER GaAs LED")
      (fields (field (name "PUBLISHER") "Altium Limited"))
      (libsource (lib "Miscellaneous Devices") (part "LED2"))
    )
    (comp (ref "D124")
      (value "LED2")
      (footprint "3.2X1.6X1.1")
      (description "Typical RED, GREEN, YELLOW, AMBER GaAs LED")
      (fields (field (name "PUBLISHER") "Altium Limited"))
      (libsource (lib "Miscellaneous Devices") (part "LED2"))
    )
    (comp (ref "D125")
      (value "LED2")
      (footprint "3.2X1.6X1.1")
      (description "Typical RED, GREEN, YELLOW, AMBER GaAs LED")
      (fields (field (name "PUBLISHER") "Altium Limited"))
      (libsource (lib "Miscellaneous Devices") (part "LED2"))
    )
    (comp (ref "D126")
      (value "LED2")
      (footprint "3.2X1.6X1.1")
      (description "Typical RED, GREEN, YELLOW, AMBER GaAs LED")
      (fields (field (name "PUBLISHER") "Altium Limited"))
      (libsource (lib "Miscellaneous Devices") (part "LED2"))
    )
    (comp (ref "D127")
      (value "LED2")
      (footprint "3.2X1.6X1.1")
      (description "Typical RED, GREEN, YELLOW, AMBER GaAs LED")
      (fields (field (name "PUBLISHER") "Altium Limited"))
      (libsource (lib "Miscellaneous Devices") (part "LED2"))
    )
    (comp (ref "D128")
      (value "LED2")
      (footprint "3.2X1.6X1.1")
      (description "Typical RED, GREEN, YELLOW, AMBER GaAs LED")
      (fields (field (name "PUBLISHER") "Altium Limited"))
      (libsource (lib "Miscellaneous Devices") (part "LED2"))
    )
    (comp (ref "D129")
      (value "LED2")
      (footprint "3.2X1.6X1.1")
      (description "Typical RED, GREEN, YELLOW, AMBER GaAs LED")
      (fields (field (name "PUBLISHER") "Altium Limited"))
      (libsource (lib "Miscellaneous Devices") (part "LED2"))
    )
    (comp (ref "D130")
      (value "LED2")
      (footprint "3.2X1.6X1.1")
      (description "Typical RED, GREEN, YELLOW, AMBER GaAs LED")
      (fields (field (name "PUBLISHER") "Altium Limited"))
      (libsource (lib "Miscellaneous Devices") (part "LED2"))
    )
    (comp (ref "D131")
      (value "LED2")
      (footprint "3.2X1.6X1.1")
      (description "Typical RED, GREEN, YELLOW, AMBER GaAs LED")
      (fields (field (name "PUBLISHER") "Altium Limited"))
      (libsource (lib "Miscellaneous Devices") (part "LED2"))
    )
    (comp (ref "D132")
      (value "LED2")
      (footprint "3.2X1.6X1.1")
      (description "Typical RED, GREEN, YELLOW, AMBER GaAs LED")
      (fields (field (name "PUBLISHER") "Altium Limited"))
      (libsource (lib "Miscellaneous Devices") (part "LED2"))
    )
    (comp (ref "D133")
      (value "LED2")
      (footprint "3.2X1.6X1.1")
      (description "Typical RED, GREEN, YELLOW, AMBER GaAs LED")
      (fields (field (name "PUBLISHER") "Altium Limited"))
      (libsource (lib "Miscellaneous Devices") (part "LED2"))
    )
    (comp (ref "D134")
      (value "LED2")
      (footprint "3.2X1.6X1.1")
      (description "Typical RED, GREEN, YELLOW, AMBER GaAs LED")
      (fields (field (name "PUBLISHER") "Altium Limited"))
      (libsource (lib "Miscellaneous Devices") (part "LED2"))
    )
    (comp (ref "D135")
      (value "LED2")
      (footprint "3.2X1.6X1.1")
      (description "Typical RED, GREEN, YELLOW, AMBER GaAs LED")
      (fields (field (name "PUBLISHER") "Altium Limited"))
      (libsource (lib "Miscellaneous Devices") (part "LED2"))
    )
    (comp (ref "D136")
      (value "LED2")
      (footprint "3.2X1.6X1.1")
      (description "Typical RED, GREEN, YELLOW, AMBER GaAs LED")
      (fields (field (name "PUBLISHER") "Altium Limited"))
      (libsource (lib "Miscellaneous Devices") (part "LED2"))
    )
    (comp (ref "D137")
      (value "LED2")
      (footprint "3.2X1.6X1.1")
      (description "Typical RED, GREEN, YELLOW, AMBER GaAs LED")
      (fields (field (name "PUBLISHER") "Altium Limited"))
      (libsource (lib "Miscellaneous Devices") (part "LED2"))
    )
    (comp (ref "D138")
      (value "LED2")
      (footprint "3.2X1.6X1.1")
      (description "Typical RED, GREEN, YELLOW, AMBER GaAs LED")
      (fields (field (name "PUBLISHER") "Altium Limited"))
      (libsource (lib "Miscellaneous Devices") (part "LED2"))
    )
    (comp (ref "D139")
      (value "LED2")
      (footprint "3.2X1.6X1.1")
      (description "Typical RED, GREEN, YELLOW, AMBER GaAs LED")
      (fields (field (name "PUBLISHER") "Altium Limited"))
      (libsource (lib "Miscellaneous Devices") (part "LED2"))
    )
    (comp (ref "D140")
      (value "LED2")
      (footprint "3.2X1.6X1.1")
      (description "Typical RED, GREEN, YELLOW, AMBER GaAs LED")
      (fields (field (name "PUBLISHER") "Altium Limited"))
      (libsource (lib "Miscellaneous Devices") (part "LED2"))
    )
    (comp (ref "D141")
      (value "LED2")
      (footprint "3.2X1.6X1.1")
      (description "Typical RED, GREEN, YELLOW, AMBER GaAs LED")
      (fields (field (name "PUBLISHER") "Altium Limited"))
      (libsource (lib "Miscellaneous Devices") (part "LED2"))
    )
    (comp (ref "D142")
      (value "LED2")
      (footprint "3.2X1.6X1.1")
      (description "Typical RED, GREEN, YELLOW, AMBER GaAs LED")
      (fields (field (name "PUBLISHER") "Altium Limited"))
      (libsource (lib "Miscellaneous Devices") (part "LED2"))
    )
    (comp (ref "D143")
      (value "LED2")
      (footprint "3.2X1.6X1.1")
      (description "Typical RED, GREEN, YELLOW, AMBER GaAs LED")
      (fields (field (name "PUBLISHER") "Altium Limited"))
      (libsource (lib "Miscellaneous Devices") (part "LED2"))
    )
    (comp (ref "D144")
      (value "LED2")
      (footprint "3.2X1.6X1.1")
      (description "Typical RED, GREEN, YELLOW, AMBER GaAs LED")
      (fields (field (name "PUBLISHER") "Altium Limited"))
      (libsource (lib "Miscellaneous Devices") (part "LED2"))
    )
    (comp (ref "D145")
      (value "LED2")
      (footprint "3.2X1.6X1.1")
      (description "Typical RED, GREEN, YELLOW, AMBER GaAs LED")
      (fields (field (name "PUBLISHER") "Altium Limited"))
      (libsource (lib "Miscellaneous Devices") (part "LED2"))
    )
    (comp (ref "D146")
      (value "LED2")
      (footprint "3.2X1.6X1.1")
      (description "Typical RED, GREEN, YELLOW, AMBER GaAs LED")
      (fields (field (name "PUBLISHER") "Altium Limited"))
      (libsource (lib "Miscellaneous Devices") (part "LED2"))
    )
    (comp (ref "D147")
      (value "LED2")
      (footprint "3.2X1.6X1.1")
      (description "Typical RED, GREEN, YELLOW, AMBER GaAs LED")
      (fields (field (name "PUBLISHER") "Altium Limited"))
      (libsource (lib "Miscellaneous Devices") (part "LED2"))
    )
    (comp (ref "D148")
      (value "LED2")
      (footprint "3.2X1.6X1.1")
      (description "Typical RED, GREEN, YELLOW, AMBER GaAs LED")
      (fields (field (name "PUBLISHER") "Altium Limited"))
      (libsource (lib "Miscellaneous Devices") (part "LED2"))
    )
    (comp (ref "D149")
      (value "LED2")
      (footprint "3.2X1.6X1.1")
      (description "Typical RED, GREEN, YELLOW, AMBER GaAs LED")
      (fields (field (name "PUBLISHER") "Altium Limited"))
      (libsource (lib "Miscellaneous Devices") (part "LED2"))
    )
    (comp (ref "D150")
      (value "LED2")
      (footprint "3.2X1.6X1.1")
      (description "Typical RED, GREEN, YELLOW, AMBER GaAs LED")
      (fields (field (name "PUBLISHER") "Altium Limited"))
      (libsource (lib "Miscellaneous Devices") (part "LED2"))
    )
    (comp (ref "D151")
      (value "LED2")
      (footprint "3.2X1.6X1.1")
      (description "Typical RED, GREEN, YELLOW, AMBER GaAs LED")
      (fields (field (name "PUBLISHER") "Altium Limited"))
      (libsource (lib "Miscellaneous Devices") (part "LED2"))
    )
    (comp (ref "D152")
      (value "LED2")
      (footprint "3.2X1.6X1.1")
      (description "Typical RED, GREEN, YELLOW, AMBER GaAs LED")
      (fields (field (name "PUBLISHER") "Altium Limited"))
      (libsource (lib "Miscellaneous Devices") (part "LED2"))
    )
    (comp (ref "D153")
      (value "LED2")
      (footprint "3.2X1.6X1.1")
      (description "Typical RED, GREEN, YELLOW, AMBER GaAs LED")
      (fields (field (name "PUBLISHER") "Altium Limited"))
      (libsource (lib "Miscellaneous Devices") (part "LED2"))
    )
    (comp (ref "D154")
      (value "LED2")
      (footprint "3.2X1.6X1.1")
      (description "Typical RED, GREEN, YELLOW, AMBER GaAs LED")
      (fields (field (name "PUBLISHER") "Altium Limited"))
      (libsource (lib "Miscellaneous Devices") (part "LED2"))
    )
    (comp (ref "D155")
      (value "LED2")
      (footprint "3.2X1.6X1.1")
      (description "Typical RED, GREEN, YELLOW, AMBER GaAs LED")
      (fields (field (name "PUBLISHER") "Altium Limited"))
      (libsource (lib "Miscellaneous Devices") (part "LED2"))
    )
    (comp (ref "D156")
      (value "LED2")
      (footprint "3.2X1.6X1.1")
      (description "Typical RED, GREEN, YELLOW, AMBER GaAs LED")
      (fields (field (name "PUBLISHER") "Altium Limited"))
      (libsource (lib "Miscellaneous Devices") (part "LED2"))
    )
    (comp (ref "D157")
      (value "LED2")
      (footprint "3.2X1.6X1.1")
      (description "Typical RED, GREEN, YELLOW, AMBER GaAs LED")
      (fields (field (name "PUBLISHER") "Altium Limited"))
      (libsource (lib "Miscellaneous Devices") (part "LED2"))
    )
    (comp (ref "D158")
      (value "LED2")
      (footprint "3.2X1.6X1.1")
      (description "Typical RED, GREEN, YELLOW, AMBER GaAs LED")
      (fields (field (name "PUBLISHER") "Altium Limited"))
      (libsource (lib "Miscellaneous Devices") (part "LED2"))
    )
    (comp (ref "D159")
      (value "LED2")
      (footprint "3.2X1.6X1.1")
      (description "Typical RED, GREEN, YELLOW, AMBER GaAs LED")
      (fields (field (name "PUBLISHER") "Altium Limited"))
      (libsource (lib "Miscellaneous Devices") (part "LED2"))
    )
    (comp (ref "D160")
      (value "LED2")
      (footprint "3.2X1.6X1.1")
      (description "Typical RED, GREEN, YELLOW, AMBER GaAs LED")
      (fields (field (name "PUBLISHER") "Altium Limited"))
      (libsource (lib "Miscellaneous Devices") (part "LED2"))
    )
    (comp (ref "D161")
      (value "LED2")
      (footprint "3.2X1.6X1.1")
      (description "Typical RED, GREEN, YELLOW, AMBER GaAs LED")
      (fields (field (name "PUBLISHER") "Altium Limited"))
      (libsource (lib "Miscellaneous Devices") (part "LED2"))
    )
    (comp (ref "D162")
      (value "LED2")
      (footprint "3.2X1.6X1.1")
      (description "Typical RED, GREEN, YELLOW, AMBER GaAs LED")
      (fields (field (name "PUBLISHER") "Altium Limited"))
      (libsource (lib "Miscellaneous Devices") (part "LED2"))
    )
    (comp (ref "D163")
      (value "LED2")
      (footprint "3.2X1.6X1.1")
      (description "Typical RED, GREEN, YELLOW, AMBER GaAs LED")
      (fields (field (name "PUBLISHER") "Altium Limited"))
      (libsource (lib "Miscellaneous Devices") (part "LED2"))
    )
    (comp (ref "D164")
      (value "LED2")
      (footprint "3.2X1.6X1.1")
      (description "Typical RED, GREEN, YELLOW, AMBER GaAs LED")
      (fields (field (name "PUBLISHER") "Altium Limited"))
      (libsource (lib "Miscellaneous Devices") (part "LED2"))
    )
    (comp (ref "D165")
      (value "LED2")
      (footprint "3.2X1.6X1.1")
      (description "Typical RED, GREEN, YELLOW, AMBER GaAs LED")
      (fields (field (name "PUBLISHER") "Altium Limited"))
      (libsource (lib "Miscellaneous Devices") (part "LED2"))
    )
    (comp (ref "D166")
      (value "LED2")
      (footprint "3.2X1.6X1.1")
      (description "Typical RED, GREEN, YELLOW, AMBER GaAs LED")
      (fields (field (name "PUBLISHER") "Altium Limited"))
      (libsource (lib "Miscellaneous Devices") (part "LED2"))
    )
    (comp (ref "D167")
      (value "LED2")
      (footprint "3.2X1.6X1.1")
      (description "Typical RED, GREEN, YELLOW, AMBER GaAs LED")
      (fields (field (name "PUBLISHER") "Altium Limited"))
      (libsource (lib "Miscellaneous Devices") (part "LED2"))
    )
    (comp (ref "D168")
      (value "LED2")
      (footprint "3.2X1.6X1.1")
      (description "Typical RED, GREEN, YELLOW, AMBER GaAs LED")
      (fields (field (name "PUBLISHER") "Altium Limited"))
      (libsource (lib "Miscellaneous Devices") (part "LED2"))
    )
    (comp (ref "D169")
      (value "LED2")
      (footprint "3.2X1.6X1.1")
      (description "Typical RED, GREEN, YELLOW, AMBER GaAs LED")
      (fields (field (name "PUBLISHER") "Altium Limited"))
      (libsource (lib "Miscellaneous Devices") (part "LED2"))
    )
    (comp (ref "D170")
      (value "LED2")
      (footprint "3.2X1.6X1.1")
      (description "Typical RED, GREEN, YELLOW, AMBER GaAs LED")
      (fields (field (name "PUBLISHER") "Altium Limited"))
      (libsource (lib "Miscellaneous Devices") (part "LED2"))
    )
    (comp (ref "D171")
      (value "LED2")
      (footprint "3.2X1.6X1.1")
      (description "Typical RED, GREEN, YELLOW, AMBER GaAs LED")
      (fields (field (name "PUBLISHER") "Altium Limited"))
      (libsource (lib "Miscellaneous Devices") (part "LED2"))
    )
    (comp (ref "D172")
      (value "LED2")
      (footprint "3.2X1.6X1.1")
      (description "Typical RED, GREEN, YELLOW, AMBER GaAs LED")
      (fields (field (name "PUBLISHER") "Altium Limited"))
      (libsource (lib "Miscellaneous Devices") (part "LED2"))
    )
    (comp (ref "D173")
      (value "LED2")
      (footprint "3.2X1.6X1.1")
      (description "Typical RED, GREEN, YELLOW, AMBER GaAs LED")
      (fields (field (name "PUBLISHER") "Altium Limited"))
      (libsource (lib "Miscellaneous Devices") (part "LED2"))
    )
    (comp (ref "D174")
      (value "LED2")
      (footprint "3.2X1.6X1.1")
      (description "Typical RED, GREEN, YELLOW, AMBER GaAs LED")
      (fields (field (name "PUBLISHER") "Altium Limited"))
      (libsource (lib "Miscellaneous Devices") (part "LED2"))
    )
    (comp (ref "D175")
      (value "LED2")
      (footprint "3.2X1.6X1.1")
      (description "Typical RED, GREEN, YELLOW, AMBER GaAs LED")
      (fields (field (name "PUBLISHER") "Altium Limited"))
      (libsource (lib "Miscellaneous Devices") (part "LED2"))
    )
    (comp (ref "D176")
      (value "LED2")
      (footprint "3.2X1.6X1.1")
      (description "Typical RED, GREEN, YELLOW, AMBER GaAs LED")
      (fields (field (name "PUBLISHER") "Altium Limited"))
      (libsource (lib "Miscellaneous Devices") (part "LED2"))
    )
    (comp (ref "D177")
      (value "LED2")
      (footprint "3.2X1.6X1.1")
      (description "Typical RED, GREEN, YELLOW, AMBER GaAs LED")
      (fields (field (name "PUBLISHER") "Altium Limited"))
      (libsource (lib "Miscellaneous Devices") (part "LED2"))
    )
    (comp (ref "D178")
      (value "LED2")
      (footprint "3.2X1.6X1.1")
      (description "Typical RED, GREEN, YELLOW, AMBER GaAs LED")
      (fields (field (name "PUBLISHER") "Altium Limited"))
      (libsource (lib "Miscellaneous Devices") (part "LED2"))
    )
    (comp (ref "D179")
      (value "LED2")
      (footprint "3.2X1.6X1.1")
      (description "Typical RED, GREEN, YELLOW, AMBER GaAs LED")
      (fields (field (name "PUBLISHER") "Altium Limited"))
      (libsource (lib "Miscellaneous Devices") (part "LED2"))
    )
    (comp (ref "D180")
      (value "LED2")
      (footprint "3.2X1.6X1.1")
      (description "Typical RED, GREEN, YELLOW, AMBER GaAs LED")
      (fields (field (name "PUBLISHER") "Altium Limited"))
      (libsource (lib "Miscellaneous Devices") (part "LED2"))
    )
    (comp (ref "D181")
      (value "LED2")
      (footprint "3.2X1.6X1.1")
      (description "Typical RED, GREEN, YELLOW, AMBER GaAs LED")
      (fields (field (name "PUBLISHER") "Altium Limited"))
      (libsource (lib "Miscellaneous Devices") (part "LED2"))
    )
    (comp (ref "D182")
      (value "LED2")
      (footprint "3.2X1.6X1.1")
      (description "Typical RED, GREEN, YELLOW, AMBER GaAs LED")
      (fields (field (name "PUBLISHER") "Altium Limited"))
      (libsource (lib "Miscellaneous Devices") (part "LED2"))
    )
    (comp (ref "D183")
      (value "LED2")
      (footprint "3.2X1.6X1.1")
      (description "Typical RED, GREEN, YELLOW, AMBER GaAs LED")
      (fields (field (name "PUBLISHER") "Altium Limited"))
      (libsource (lib "Miscellaneous Devices") (part "LED2"))
    )
    (comp (ref "D184")
      (value "LED2")
      (footprint "3.2X1.6X1.1")
      (description "Typical RED, GREEN, YELLOW, AMBER GaAs LED")
      (fields (field (name "PUBLISHER") "Altium Limited"))
      (libsource (lib "Miscellaneous Devices") (part "LED2"))
    )
    (comp (ref "D185")
      (value "LED2")
      (footprint "3.2X1.6X1.1")
      (description "Typical RED, GREEN, YELLOW, AMBER GaAs LED")
      (fields (field (name "PUBLISHER") "Altium Limited"))
      (libsource (lib "Miscellaneous Devices") (part "LED2"))
    )
    (comp (ref "D186")
      (value "LED2")
      (footprint "3.2X1.6X1.1")
      (description "Typical RED, GREEN, YELLOW, AMBER GaAs LED")
      (fields (field (name "PUBLISHER") "Altium Limited"))
      (libsource (lib "Miscellaneous Devices") (part "LED2"))
    )
    (comp (ref "D187")
      (value "LED2")
      (footprint "3.2X1.6X1.1")
      (description "Typical RED, GREEN, YELLOW, AMBER GaAs LED")
      (fields (field (name "PUBLISHER") "Altium Limited"))
      (libsource (lib "Miscellaneous Devices") (part "LED2"))
    )
    (comp (ref "D188")
      (value "LED2")
      (footprint "3.2X1.6X1.1")
      (description "Typical RED, GREEN, YELLOW, AMBER GaAs LED")
      (fields (field (name "PUBLISHER") "Altium Limited"))
      (libsource (lib "Miscellaneous Devices") (part "LED2"))
    )
    (comp (ref "D189")
      (value "LED2")
      (footprint "3.2X1.6X1.1")
      (description "Typical RED, GREEN, YELLOW, AMBER GaAs LED")
      (fields (field (name "PUBLISHER") "Altium Limited"))
      (libsource (lib "Miscellaneous Devices") (part "LED2"))
    )
    (comp (ref "D190")
      (value "LED2")
      (footprint "3.2X1.6X1.1")
      (description "Typical RED, GREEN, YELLOW, AMBER GaAs LED")
      (fields (field (name "PUBLISHER") "Altium Limited"))
      (libsource (lib "Miscellaneous Devices") (part "LED2"))
    )
    (comp (ref "D191")
      (value "LED2")
      (footprint "3.2X1.6X1.1")
      (description "Typical RED, GREEN, YELLOW, AMBER GaAs LED")
      (fields (field (name "PUBLISHER") "Altium Limited"))
      (libsource (lib "Miscellaneous Devices") (part "LED2"))
    )
    (comp (ref "D192")
      (value "LED2")
      (footprint "3.2X1.6X1.1")
      (description "Typical RED, GREEN, YELLOW, AMBER GaAs LED")
      (fields (field (name "PUBLISHER") "Altium Limited"))
      (libsource (lib "Miscellaneous Devices") (part "LED2"))
    )
    (comp (ref "D193")
      (value "LED2")
      (footprint "3.2X1.6X1.1")
      (description "Typical RED, GREEN, YELLOW, AMBER GaAs LED")
      (fields (field (name "PUBLISHER") "Altium Limited"))
      (libsource (lib "Miscellaneous Devices") (part "LED2"))
    )
    (comp (ref "D194")
      (value "LED2")
      (footprint "3.2X1.6X1.1")
      (description "Typical RED, GREEN, YELLOW, AMBER GaAs LED")
      (fields (field (name "PUBLISHER") "Altium Limited"))
      (libsource (lib "Miscellaneous Devices") (part "LED2"))
    )
    (comp (ref "D195")
      (value "LED2")
      (footprint "3.2X1.6X1.1")
      (description "Typical RED, GREEN, YELLOW, AMBER GaAs LED")
      (fields (field (name "PUBLISHER") "Altium Limited"))
      (libsource (lib "Miscellaneous Devices") (part "LED2"))
    )
    (comp (ref "D196")
      (value "LED2")
      (footprint "3.2X1.6X1.1")
      (description "Typical RED, GREEN, YELLOW, AMBER GaAs LED")
      (fields (field (name "PUBLISHER") "Altium Limited"))
      (libsource (lib "Miscellaneous Devices") (part "LED2"))
    )
    (comp (ref "D197")
      (value "LED2")
      (footprint "3.2X1.6X1.1")
      (description "Typical RED, GREEN, YELLOW, AMBER GaAs LED")
      (fields (field (name "PUBLISHER") "Altium Limited"))
      (libsource (lib "Miscellaneous Devices") (part "LED2"))
    )
    (comp (ref "D198")
      (value "LED2")
      (footprint "3.2X1.6X1.1")
      (description "Typical RED, GREEN, YELLOW, AMBER GaAs LED")
      (fields (field (name "PUBLISHER") "Altium Limited"))
      (libsource (lib "Miscellaneous Devices") (part "LED2"))
    )
    (comp (ref "D199")
      (value "LED2")
      (footprint "3.2X1.6X1.1")
      (description "Typical RED, GREEN, YELLOW, AMBER GaAs LED")
      (fields (field (name "PUBLISHER") "Altium Limited"))
      (libsource (lib "Miscellaneous Devices") (part "LED2"))
    )
    (comp (ref "D200")
      (value "LED2")
      (footprint "3.2X1.6X1.1")
      (description "Typical RED, GREEN, YELLOW, AMBER GaAs LED")
      (fields (field (name "PUBLISHER") "Altium Limited"))
      (libsource (lib "Miscellaneous Devices") (part "LED2"))
    )
    (comp (ref "D201")
      (value "LED2")
      (footprint "3.2X1.6X1.1")
      (description "Typical RED, GREEN, YELLOW, AMBER GaAs LED")
      (fields (field (name "PUBLISHER") "Altium Limited"))
      (libsource (lib "Miscellaneous Devices") (part "LED2"))
    )
    (comp (ref "D202")
      (value "LED2")
      (footprint "3.2X1.6X1.1")
      (description "Typical RED, GREEN, YELLOW, AMBER GaAs LED")
      (fields (field (name "PUBLISHER") "Altium Limited"))
      (libsource (lib "Miscellaneous Devices") (part "LED2"))
    )
    (comp (ref "D203")
      (value "LED2")
      (footprint "3.2X1.6X1.1")
      (description "Typical RED, GREEN, YELLOW, AMBER GaAs LED")
      (fields (field (name "PUBLISHER") "Altium Limited"))
      (libsource (lib "Miscellaneous Devices") (part "LED2"))
    )
    (comp (ref "D204")
      (value "LED2")
      (footprint "3.2X1.6X1.1")
      (description "Typical RED, GREEN, YELLOW, AMBER GaAs LED")
      (fields (field (name "PUBLISHER") "Altium Limited"))
      (libsource (lib "Miscellaneous Devices") (part "LED2"))
    )
    (comp (ref "D205")
      (value "LED2")
      (footprint "3.2X1.6X1.1")
      (description "Typical RED, GREEN, YELLOW, AMBER GaAs LED")
      (fields (field (name "PUBLISHER") "Altium Limited"))
      (libsource (lib "Miscellaneous Devices") (part "LED2"))
    )
    (comp (ref "D206")
      (value "LED2")
      (footprint "3.2X1.6X1.1")
      (description "Typical RED, GREEN, YELLOW, AMBER GaAs LED")
      (fields (field (name "PUBLISHER") "Altium Limited"))
      (libsource (lib "Miscellaneous Devices") (part "LED2"))
    )
    (comp (ref "D207")
      (value "LED2")
      (footprint "3.2X1.6X1.1")
      (description "Typical RED, GREEN, YELLOW, AMBER GaAs LED")
      (fields (field (name "PUBLISHER") "Altium Limited"))
      (libsource (lib "Miscellaneous Devices") (part "LED2"))
    )
    (comp (ref "D208")
      (value "LED2")
      (footprint "3.2X1.6X1.1")
      (description "Typical RED, GREEN, YELLOW, AMBER GaAs LED")
      (fields (field (name "PUBLISHER") "Altium Limited"))
      (libsource (lib "Miscellaneous Devices") (part "LED2"))
    )
    (comp (ref "D209")
      (value "LED2")
      (footprint "3.2X1.6X1.1")
      (description "Typical RED, GREEN, YELLOW, AMBER GaAs LED")
      (fields (field (name "PUBLISHER") "Altium Limited"))
      (libsource (lib "Miscellaneous Devices") (part "LED2"))
    )
    (comp (ref "D210")
      (value "LED2")
      (footprint "3.2X1.6X1.1")
      (description "Typical RED, GREEN, YELLOW, AMBER GaAs LED")
      (fields (field (name "PUBLISHER") "Altium Limited"))
      (libsource (lib "Miscellaneous Devices") (part "LED2"))
    )
    (comp (ref "D211")
      (value "LED2")
      (footprint "3.2X1.6X1.1")
      (description "Typical RED, GREEN, YELLOW, AMBER GaAs LED")
      (fields (field (name "PUBLISHER") "Altium Limited"))
      (libsource (lib "Miscellaneous Devices") (part "LED2"))
    )
    (comp (ref "D212")
      (value "LED2")
      (footprint "3.2X1.6X1.1")
      (description "Typical RED, GREEN, YELLOW, AMBER GaAs LED")
      (fields (field (name "PUBLISHER") "Altium Limited"))
      (libsource (lib "Miscellaneous Devices") (part "LED2"))
    )
    (comp (ref "D213")
      (value "LED2")
      (footprint "3.2X1.6X1.1")
      (description "Typical RED, GREEN, YELLOW, AMBER GaAs LED")
      (fields (field (name "PUBLISHER") "Altium Limited"))
      (libsource (lib "Miscellaneous Devices") (part "LED2"))
    )
    (comp (ref "D214")
      (value "LED2")
      (footprint "3.2X1.6X1.1")
      (description "Typical RED, GREEN, YELLOW, AMBER GaAs LED")
      (fields (field (name "PUBLISHER") "Altium Limited"))
      (libsource (lib "Miscellaneous Devices") (part "LED2"))
    )
    (comp (ref "D215")
      (value "LED2")
      (footprint "3.2X1.6X1.1")
      (description "Typical RED, GREEN, YELLOW, AMBER GaAs LED")
      (fields (field (name "PUBLISHER") "Altium Limited"))
      (libsource (lib "Miscellaneous Devices") (part "LED2"))
    )
    (comp (ref "D216")
      (value "LED2")
      (footprint "3.2X1.6X1.1")
      (description "Typical RED, GREEN, YELLOW, AMBER GaAs LED")
      (fields (field (name "PUBLISHER") "Altium Limited"))
      (libsource (lib "Miscellaneous Devices") (part "LED2"))
    )
    (comp (ref "D217")
      (value "LED2")
      (footprint "3.2X1.6X1.1")
      (description "Typical RED, GREEN, YELLOW, AMBER GaAs LED")
      (fields (field (name "PUBLISHER") "Altium Limited"))
      (libsource (lib "Miscellaneous Devices") (part "LED2"))
    )
    (comp (ref "D218")
      (value "LED2")
      (footprint "3.2X1.6X1.1")
      (description "Typical RED, GREEN, YELLOW, AMBER GaAs LED")
      (fields (field (name "PUBLISHER") "Altium Limited"))
      (libsource (lib "Miscellaneous Devices") (part "LED2"))
    )
    (comp (ref "D219")
      (value "LED2")
      (footprint "3.2X1.6X1.1")
      (description "Typical RED, GREEN, YELLOW, AMBER GaAs LED")
      (fields (field (name "PUBLISHER") "Altium Limited"))
      (libsource (lib "Miscellaneous Devices") (part "LED2"))
    )
    (comp (ref "D220")
      (value "LED2")
      (footprint "3.2X1.6X1.1")
      (description "Typical RED, GREEN, YELLOW, AMBER GaAs LED")
      (fields (field (name "PUBLISHER") "Altium Limited"))
      (libsource (lib "Miscellaneous Devices") (part "LED2"))
    )
    (comp (ref "D221")
      (value "LED2")
      (footprint "3.2X1.6X1.1")
      (description "Typical RED, GREEN, YELLOW, AMBER GaAs LED")
      (fields (field (name "PUBLISHER") "Altium Limited"))
      (libsource (lib "Miscellaneous Devices") (part "LED2"))
    )
    (comp (ref "D222")
      (value "LED2")
      (footprint "3.2X1.6X1.1")
      (description "Typical RED, GREEN, YELLOW, AMBER GaAs LED")
      (fields (field (name "PUBLISHER") "Altium Limited"))
      (libsource (lib "Miscellaneous Devices") (part "LED2"))
    )
    (comp (ref "D223")
      (value "LED2")
      (footprint "3.2X1.6X1.1")
      (description "Typical RED, GREEN, YELLOW, AMBER GaAs LED")
      (fields (field (name "PUBLISHER") "Altium Limited"))
      (libsource (lib "Miscellaneous Devices") (part "LED2"))
    )
    (comp (ref "D224")
      (value "LED2")
      (footprint "3.2X1.6X1.1")
      (description "Typical RED, GREEN, YELLOW, AMBER GaAs LED")
      (fields (field (name "PUBLISHER") "Altium Limited"))
      (libsource (lib "Miscellaneous Devices") (part "LED2"))
    )
    (comp (ref "D225")
      (value "LED2")
      (footprint "3.2X1.6X1.1")
      (description "Typical RED, GREEN, YELLOW, AMBER GaAs LED")
      (fields (field (name "PUBLISHER") "Altium Limited"))
      (libsource (lib "Miscellaneous Devices") (part "LED2"))
    )
    (comp (ref "D226")
      (value "LED2")
      (footprint "3.2X1.6X1.1")
      (description "Typical RED, GREEN, YELLOW, AMBER GaAs LED")
      (fields (field (name "PUBLISHER") "Altium Limited"))
      (libsource (lib "Miscellaneous Devices") (part "LED2"))
    )
    (comp (ref "D227")
      (value "LED2")
      (footprint "3.2X1.6X1.1")
      (description "Typical RED, GREEN, YELLOW, AMBER GaAs LED")
      (fields (field (name "PUBLISHER") "Altium Limited"))
      (libsource (lib "Miscellaneous Devices") (part "LED2"))
    )
    (comp (ref "D228")
      (value "LED2")
      (footprint "3.2X1.6X1.1")
      (description "Typical RED, GREEN, YELLOW, AMBER GaAs LED")
      (fields (field (name "PUBLISHER") "Altium Limited"))
      (libsource (lib "Miscellaneous Devices") (part "LED2"))
    )
    (comp (ref "D229")
      (value "LED2")
      (footprint "3.2X1.6X1.1")
      (description "Typical RED, GREEN, YELLOW, AMBER GaAs LED")
      (fields (field (name "PUBLISHER") "Altium Limited"))
      (libsource (lib "Miscellaneous Devices") (part "LED2"))
    )
    (comp (ref "D230")
      (value "LED2")
      (footprint "3.2X1.6X1.1")
      (description "Typical RED, GREEN, YELLOW, AMBER GaAs LED")
      (fields (field (name "PUBLISHER") "Altium Limited"))
      (libsource (lib "Miscellaneous Devices") (part "LED2"))
    )
    (comp (ref "D231")
      (value "LED2")
      (footprint "3.2X1.6X1.1")
      (description "Typical RED, GREEN, YELLOW, AMBER GaAs LED")
      (fields (field (name "PUBLISHER") "Altium Limited"))
      (libsource (lib "Miscellaneous Devices") (part "LED2"))
    )
    (comp (ref "D232")
      (value "LED2")
      (footprint "3.2X1.6X1.1")
      (description "Typical RED, GREEN, YELLOW, AMBER GaAs LED")
      (fields (field (name "PUBLISHER") "Altium Limited"))
      (libsource (lib "Miscellaneous Devices") (part "LED2"))
    )
    (comp (ref "D233")
      (value "LED2")
      (footprint "3.2X1.6X1.1")
      (description "Typical RED, GREEN, YELLOW, AMBER GaAs LED")
      (fields (field (name "PUBLISHER") "Altium Limited"))
      (libsource (lib "Miscellaneous Devices") (part "LED2"))
    )
    (comp (ref "D234")
      (value "LED2")
      (footprint "3.2X1.6X1.1")
      (description "Typical RED, GREEN, YELLOW, AMBER GaAs LED")
      (fields (field (name "PUBLISHER") "Altium Limited"))
      (libsource (lib "Miscellaneous Devices") (part "LED2"))
    )
    (comp (ref "D235")
      (value "LED2")
      (footprint "3.2X1.6X1.1")
      (description "Typical RED, GREEN, YELLOW, AMBER GaAs LED")
      (fields (field (name "PUBLISHER") "Altium Limited"))
      (libsource (lib "Miscellaneous Devices") (part "LED2"))
    )
    (comp (ref "D236")
      (value "LED2")
      (footprint "3.2X1.6X1.1")
      (description "Typical RED, GREEN, YELLOW, AMBER GaAs LED")
      (fields (field (name "PUBLISHER") "Altium Limited"))
      (libsource (lib "Miscellaneous Devices") (part "LED2"))
    )
    (comp (ref "D237")
      (value "LED2")
      (footprint "3.2X1.6X1.1")
      (description "Typical RED, GREEN, YELLOW, AMBER GaAs LED")
      (fields (field (name "PUBLISHER") "Altium Limited"))
      (libsource (lib "Miscellaneous Devices") (part "LED2"))
    )
    (comp (ref "D238")
      (value "LED2")
      (footprint "3.2X1.6X1.1")
      (description "Typical RED, GREEN, YELLOW, AMBER GaAs LED")
      (fields (field (name "PUBLISHER") "Altium Limited"))
      (libsource (lib "Miscellaneous Devices") (part "LED2"))
    )
    (comp (ref "D239")
      (value "LED2")
      (footprint "3.2X1.6X1.1")
      (description "Typical RED, GREEN, YELLOW, AMBER GaAs LED")
      (fields (field (name "PUBLISHER") "Altium Limited"))
      (libsource (lib "Miscellaneous Devices") (part "LED2"))
    )
    (comp (ref "D240")
      (value "LED2")
      (footprint "3.2X1.6X1.1")
      (description "Typical RED, GREEN, YELLOW, AMBER GaAs LED")
      (fields (field (name "PUBLISHER") "Altium Limited"))
      (libsource (lib "Miscellaneous Devices") (part "LED2"))
    )
    (comp (ref "D241")
      (value "LED2")
      (footprint "3.2X1.6X1.1")
      (description "Typical RED, GREEN, YELLOW, AMBER GaAs LED")
      (fields (field (name "PUBLISHER") "Altium Limited"))
      (libsource (lib "Miscellaneous Devices") (part "LED2"))
    )
    (comp (ref "D242")
      (value "LED2")
      (footprint "3.2X1.6X1.1")
      (description "Typical RED, GREEN, YELLOW, AMBER GaAs LED")
      (fields (field (name "PUBLISHER") "Altium Limited"))
      (libsource (lib "Miscellaneous Devices") (part "LED2"))
    )
    (comp (ref "D243")
      (value "LED2")
      (footprint "3.2X1.6X1.1")
      (description "Typical RED, GREEN, YELLOW, AMBER GaAs LED")
      (fields (field (name "PUBLISHER") "Altium Limited"))
      (libsource (lib "Miscellaneous Devices") (part "LED2"))
    )
    (comp (ref "D244")
      (value "LED2")
      (footprint "3.2X1.6X1.1")
      (description "Typical RED, GREEN, YELLOW, AMBER GaAs LED")
      (fields (field (name "PUBLISHER") "Altium Limited"))
      (libsource (lib "Miscellaneous Devices") (part "LED2"))
    )
    (comp (ref "D245")
      (value "LED2")
      (footprint "3.2X1.6X1.1")
      (description "Typical RED, GREEN, YELLOW, AMBER GaAs LED")
      (fields (field (name "PUBLISHER") "Altium Limited"))
      (libsource (lib "Miscellaneous Devices") (part "LED2"))
    )
    (comp (ref "D246")
      (value "LED2")
      (footprint "3.2X1.6X1.1")
      (description "Typical RED, GREEN, YELLOW, AMBER GaAs LED")
      (fields (field (name "PUBLISHER") "Altium Limited"))
      (libsource (lib "Miscellaneous Devices") (part "LED2"))
    )
    (comp (ref "D247")
      (value "LED2")
      (footprint "3.2X1.6X1.1")
      (description "Typical RED, GREEN, YELLOW, AMBER GaAs LED")
      (fields (field (name "PUBLISHER") "Altium Limited"))
      (libsource (lib "Miscellaneous Devices") (part "LED2"))
    )
    (comp (ref "D248")
      (value "LED2")
      (footprint "3.2X1.6X1.1")
      (description "Typical RED, GREEN, YELLOW, AMBER GaAs LED")
      (fields (field (name "PUBLISHER") "Altium Limited"))
      (libsource (lib "Miscellaneous Devices") (part "LED2"))
    )
    (comp (ref "D249")
      (value "LED2")
      (footprint "3.2X1.6X1.1")
      (description "Typical RED, GREEN, YELLOW, AMBER GaAs LED")
      (fields (field (name "PUBLISHER") "Altium Limited"))
      (libsource (lib "Miscellaneous Devices") (part "LED2"))
    )
    (comp (ref "D250")
      (value "LED2")
      (footprint "3.2X1.6X1.1")
      (description "Typical RED, GREEN, YELLOW, AMBER GaAs LED")
      (fields (field (name "PUBLISHER") "Altium Limited"))
      (libsource (lib "Miscellaneous Devices") (part "LED2"))
    )
    (comp (ref "D251")
      (value "LED2")
      (footprint "3.2X1.6X1.1")
      (description "Typical RED, GREEN, YELLOW, AMBER GaAs LED")
      (fields (field (name "PUBLISHER") "Altium Limited"))
      (libsource (lib "Miscellaneous Devices") (part "LED2"))
    )
    (comp (ref "D252")
      (value "LED2")
      (footprint "3.2X1.6X1.1")
      (description "Typical RED, GREEN, YELLOW, AMBER GaAs LED")
      (fields (field (name "PUBLISHER") "Altium Limited"))
      (libsource (lib "Miscellaneous Devices") (part "LED2"))
    )
    (comp (ref "D253")
      (value "LED2")
      (footprint "3.2X1.6X1.1")
      (description "Typical RED, GREEN, YELLOW, AMBER GaAs LED")
      (fields (field (name "PUBLISHER") "Altium Limited"))
      (libsource (lib "Miscellaneous Devices") (part "LED2"))
    )
    (comp (ref "D254")
      (value "LED2")
      (footprint "3.2X1.6X1.1")
      (description "Typical RED, GREEN, YELLOW, AMBER GaAs LED")
      (fields (field (name "PUBLISHER") "Altium Limited"))
      (libsource (lib "Miscellaneous Devices") (part "LED2"))
    )
    (comp (ref "D255")
      (value "LED2")
      (footprint "3.2X1.6X1.1")
      (description "Typical RED, GREEN, YELLOW, AMBER GaAs LED")
      (fields (field (name "PUBLISHER") "Altium Limited"))
      (libsource (lib "Miscellaneous Devices") (part "LED2"))
    )
    (comp (ref "D256")
      (value "LED2")
      (footprint "3.2X1.6X1.1")
      (description "Typical RED, GREEN, YELLOW, AMBER GaAs LED")
      (fields (field (name "PUBLISHER") "Altium Limited"))
      (libsource (lib "Miscellaneous Devices") (part "LED2"))
    )
  )
  (nets
    (net (code "1") (name "Net-(D1-A)") (class "Default")
      (node (ref "Anodos1") (pin "1") (pinfunction "1_1") (pintype "passive"))
      (node (ref "Anodos2") (pin "1") (pinfunction "1_1") (pintype "passive"))
      (node (ref "D1") (pin "1") (pinfunction "A_1") (pintype "passive"))
      (node (ref "D10") (pin "1") (pinfunction "A_1") (pintype "passive"))
      (node (ref "D11") (pin "1") (pinfunction "A_1") (pintype "passive"))
      (node (ref "D12") (pin "1") (pinfunction "A_1") (pintype "passive"))
      (node (ref "D13") (pin "1") (pinfunction "A_1") (pintype "passive"))
      (node (ref "D14") (pin "1") (pinfunction "A_1") (pintype "passive"))
      (node (ref "D15") (pin "1") (pinfunction "A_1") (pintype "passive"))
      (node (ref "D16") (pin "1") (pinfunction "A_1") (pintype "passive"))
      (node (ref "D2") (pin "1") (pinfunction "A_1") (pintype "passive"))
      (node (ref "D3") (pin "1") (pinfunction "A_1") (pintype "passive"))
      (node (ref "D4") (pin "1") (pinfunction "A_1") (pintype "passive"))
      (node (ref "D5") (pin "1") (pinfunction "A_1") (pintype "passive"))
      (node (ref "D6") (pin "1") (pinfunction "A_1") (pintype "passive"))
      (node (ref "D7") (pin "1") (pinfunction "A_1") (pintype "passive"))
      (node (ref "D8") (pin "1") (pinfunction "A_1") (pintype "passive"))
      (node (ref "D9") (pin "1") (pinfunction "A_1") (pintype "passive"))
    )
    (net (code "2") (name "Net-(D1-K)") (class "Default")
      (node (ref "Catodos1") (pin "1") (pinfunction "1_1") (pintype "passive"))
      (node (ref "D1") (pin "2") (pinfunction "K_2") (pintype "passive"))
      (node (ref "D113") (pin "2") (pinfunction "K_2") (pintype "passive"))
      (node (ref "D129") (pin "2") (pinfunction "K_2") (pintype "passive"))
      (node (ref "D145") (pin "2") (pinfunction "K_2") (pintype "passive"))
      (node (ref "D161") (pin "2") (pinfunction "K_2") (pintype "passive"))
      (node (ref "D17") (pin "2") (pinfunction "K_2") (pintype "passive"))
      (node (ref "D177") (pin "2") (pinfunction "K_2") (pintype "passive"))
      (node (ref "D193") (pin "2") (pinfunction "K_2") (pintype "passive"))
      (node (ref "D209") (pin "2") (pinfunction "K_2") (pintype "passive"))
      (node (ref "D225") (pin "2") (pinfunction "K_2") (pintype "passive"))
      (node (ref "D241") (pin "2") (pinfunction "K_2") (pintype "passive"))
      (node (ref "D33") (pin "2") (pinfunction "K_2") (pintype "passive"))
      (node (ref "D49") (pin "2") (pinfunction "K_2") (pintype "passive"))
      (node (ref "D65") (pin "2") (pinfunction "K_2") (pintype "passive"))
      (node (ref "D81") (pin "2") (pinfunction "K_2") (pintype "passive"))
      (node (ref "D97") (pin "2") (pinfunction "K_2") (pintype "passive"))
    )
    (net (code "3") (name "Net-(D10-K)") (class "Default")
      (node (ref "Catodos1") (pin "10") (pinfunction "10_10") (pintype "passive"))
      (node (ref "D10") (pin "2") (pinfunction "K_2") (pintype "passive"))
      (node (ref "D106") (pin "2") (pinfunction "K_2") (pintype "passive"))
      (node (ref "D122") (pin "2") (pinfunction "K_2") (pintype "passive"))
      (node (ref "D138") (pin "2") (pinfunction "K_2") (pintype "passive"))
      (node (ref "D154") (pin "2") (pinfunction "K_2") (pintype "passive"))
      (node (ref "D170") (pin "2") (pinfunction "K_2") (pintype "passive"))
      (node (ref "D186") (pin "2") (pinfunction "K_2") (pintype "passive"))
      (node (ref "D202") (pin "2") (pinfunction "K_2") (pintype "passive"))
      (node (ref "D218") (pin "2") (pinfunction "K_2") (pintype "passive"))
      (node (ref "D234") (pin "2") (pinfunction "K_2") (pintype "passive"))
      (node (ref "D250") (pin "2") (pinfunction "K_2") (pintype "passive"))
      (node (ref "D26") (pin "2") (pinfunction "K_2") (pintype "passive"))
      (node (ref "D42") (pin "2") (pinfunction "K_2") (pintype "passive"))
      (node (ref "D58") (pin "2") (pinfunction "K_2") (pintype "passive"))
      (node (ref "D74") (pin "2") (pinfunction "K_2") (pintype "passive"))
      (node (ref "D90") (pin "2") (pinfunction "K_2") (pintype "passive"))
    )
    (net (code "4") (name "Net-(D17-A)") (class "Default")
      (node (ref "Anodos1") (pin "2") (pinfunction "2_2") (pintype "passive"))
      (node (ref "Anodos2") (pin "2") (pinfunction "2_2") (pintype "passive"))
      (node (ref "D17") (pin "1") (pinfunction "A_1") (pintype "passive"))
      (node (ref "D18") (pin "1") (pinfunction "A_1") (pintype "passive"))
      (node (ref "D19") (pin "1") (pinfunction "A_1") (pintype "passive"))
      (node (ref "D20") (pin "1") (pinfunction "A_1") (pintype "passive"))
      (node (ref "D21") (pin "1") (pinfunction "A_1") (pintype "passive"))
      (node (ref "D22") (pin "1") (pinfunction "A_1") (pintype "passive"))
      (node (ref "D23") (pin "1") (pinfunction "A_1") (pintype "passive"))
      (node (ref "D24") (pin "1") (pinfunction "A_1") (pintype "passive"))
      (node (ref "D25") (pin "1") (pinfunction "A_1") (pintype "passive"))
      (node (ref "D26") (pin "1") (pinfunction "A_1") (pintype "passive"))
      (node (ref "D27") (pin "1") (pinfunction "A_1") (pintype "passive"))
      (node (ref "D28") (pin "1") (pinfunction "A_1") (pintype "passive"))
      (node (ref "D29") (pin "1") (pinfunction "A_1") (pintype "passive"))
      (node (ref "D30") (pin "1") (pinfunction "A_1") (pintype "passive"))
      (node (ref "D31") (pin "1") (pinfunction "A_1") (pintype "passive"))
      (node (ref "D32") (pin "1") (pinfunction "A_1") (pintype "passive"))
    )
    (net (code "5") (name "Net-(D33-A)") (class "Default")
      (node (ref "Anodos1") (pin "3") (pinfunction "3_3") (pintype "passive"))
      (node (ref "Anodos2") (pin "3") (pinfunction "3_3") (pintype "passive"))
      (node (ref "D33") (pin "1") (pinfunction "A_1") (pintype "passive"))
      (node (ref "D34") (pin "1") (pinfunction "A_1") (pintype "passive"))
      (node (ref "D35") (pin "1") (pinfunction "A_1") (pintype "passive"))
      (node (ref "D36") (pin "1") (pinfunction "A_1") (pintype "passive"))
      (node (ref "D37") (pin "1") (pinfunction "A_1") (pintype "passive"))
      (node (ref "D38") (pin "1") (pinfunction "A_1") (pintype "passive"))
      (node (ref "D39") (pin "1") (pinfunction "A_1") (pintype "passive"))
      (node (ref "D40") (pin "1") (pinfunction "A_1") (pintype "passive"))
      (node (ref "D41") (pin "1") (pinfunction "A_1") (pintype "passive"))
      (node (ref "D42") (pin "1") (pinfunction "A_1") (pintype "passive"))
      (node (ref "D43") (pin "1") (pinfunction "A_1") (pintype "passive"))
      (node (ref "D44") (pin "1") (pinfunction "A_1") (pintype "passive"))
      (node (ref "D45") (pin "1") (pinfunction "A_1") (pintype "passive"))
      (node (ref "D46") (pin "1") (pinfunction "A_1") (pintype "passive"))
      (node (ref "D47") (pin "1") (pinfunction "A_1") (pintype "passive"))
      (node (ref "D48") (pin "1") (pinfunction "A_1") (pintype "passive"))
    )
    (net (code "6") (name "Net-(D49-A)") (class "Default")
      (node (ref "Anodos1") (pin "4") (pinfunction "4_4") (pintype "passive"))
      (node (ref "Anodos2") (pin "4") (pinfunction "4_4") (pintype "passive"))
      (node (ref "D49") (pin "1") (pinfunction "A_1") (pintype "passive"))
      (node (ref "D50") (pin "1") (pinfunction "A_1") (pintype "passive"))
      (node (ref "D51") (pin "1") (pinfunction "A_1") (pintype "passive"))
      (node (ref "D52") (pin "1") (pinfunction "A_1") (pintype "passive"))
      (node (ref "D53") (pin "1") (pinfunction "A_1") (pintype "passive"))
      (node (ref "D54") (pin "1") (pinfunction "A_1") (pintype "passive"))
      (node (ref "D55") (pin "1") (pinfunction "A_1") (pintype "passive"))
      (node (ref "D56") (pin "1") (pinfunction "A_1") (pintype "passive"))
      (node (ref "D57") (pin "1") (pinfunction "A_1") (pintype "passive"))
      (node (ref "D58") (pin "1") (pinfunction "A_1") (pintype "passive"))
      (node (ref "D59") (pin "1") (pinfunction "A_1") (pintype "passive"))
      (node (ref "D60") (pin "1") (pinfunction "A_1") (pintype "passive"))
      (node (ref "D61") (pin "1") (pinfunction "A_1") (pintype "passive"))
      (node (ref "D62") (pin "1") (pinfunction "A_1") (pintype "passive"))
      (node (ref "D63") (pin "1") (pinfunction "A_1") (pintype "passive"))
      (node (ref "D64") (pin "1") (pinfunction "A_1") (pintype "passive"))
    )
    (net (code "7") (name "Net-(D65-A)") (class "Default")
      (node (ref "Anodos1") (pin "5") (pinfunction "5_5") (pintype "passive"))
      (node (ref "Anodos2") (pin "5") (pinfunction "5_5") (pintype "passive"))
      (node (ref "D65") (pin "1") (pinfunction "A_1") (pintype "passive"))
      (node (ref "D66") (pin "1") (pinfunction "A_1") (pintype "passive"))
      (node (ref "D67") (pin "1") (pinfunction "A_1") (pintype "passive"))
      (node (ref "D68") (pin "1") (pinfunction "A_1") (pintype "passive"))
      (node (ref "D69") (pin "1") (pinfunction "A_1") (pintype "passive"))
      (node (ref "D70") (pin "1") (pinfunction "A_1") (pintype "passive"))
      (node (ref "D71") (pin "1") (pinfunction "A_1") (pintype "passive"))
      (node (ref "D72") (pin "1") (pinfunction "A_1") (pintype "passive"))
      (node (ref "D73") (pin "1") (pinfunction "A_1") (pintype "passive"))
      (node (ref "D74") (pin "1") (pinfunction "A_1") (pintype "passive"))
      (node (ref "D75") (pin "1") (pinfunction "A_1") (pintype "passive"))
      (node (ref "D76") (pin "1") (pinfunction "A_1") (pintype "passive"))
      (node (ref "D77") (pin "1") (pinfunction "A_1") (pintype "passive"))
      (node (ref "D78") (pin "1") (pinfunction "A_1") (pintype "passive"))
      (node (ref "D79") (pin "1") (pinfunction "A_1") (pintype "passive"))
      (node (ref "D80") (pin "1") (pinfunction "A_1") (pintype "passive"))
    )
    (net (code "8") (name "Net-(D81-A)") (class "Default")
      (node (ref "Anodos1") (pin "6") (pinfunction "6_6") (pintype "passive"))
      (node (ref "Anodos2") (pin "6") (pinfunction "6_6") (pintype "passive"))
      (node (ref "D81") (pin "1") (pinfunction "A_1") (pintype "passive"))
      (node (ref "D82") (pin "1") (pinfunction "A_1") (pintype "passive"))
      (node (ref "D83") (pin "1") (pinfunction "A_1") (pintype "passive"))
      (node (ref "D84") (pin "1") (pinfunction "A_1") (pintype "passive"))
      (node (ref "D85") (pin "1") (pinfunction "A_1") (pintype "passive"))
      (node (ref "D86") (pin "1") (pinfunction "A_1") (pintype "passive"))
      (node (ref "D87") (pin "1") (pinfunction "A_1") (pintype "passive"))
      (node (ref "D88") (pin "1") (pinfunction "A_1") (pintype "passive"))
      (node (ref "D89") (pin "1") (pinfunction "A_1") (pintype "passive"))
      (node (ref "D90") (pin "1") (pinfunction "A_1") (pintype "passive"))
      (node (ref "D91") (pin "1") (pinfunction "A_1") (pintype "passive"))
      (node (ref "D92") (pin "1") (pinfunction "A_1") (pintype "passive"))
      (node (ref "D93") (pin "1") (pinfunction "A_1") (pintype "passive"))
      (node (ref "D94") (pin "1") (pinfunction "A_1") (pintype "passive"))
      (node (ref "D95") (pin "1") (pinfunction "A_1") (pintype "passive"))
      (node (ref "D96") (pin "1") (pinfunction "A_1") (pintype "passive"))
    )
    (net (code "9") (name "Net-(D100-A)") (class "Default")
      (node (ref "Anodos1") (pin "7") (pinfunction "7_7") (pintype "passive"))
      (node (ref "Anodos2") (pin "7") (pinfunction "7_7") (pintype "passive"))
      (node (ref "D100") (pin "1") (pinfunction "A_1") (pintype "passive"))
      (node (ref "D101") (pin "1") (pinfunction "A_1") (pintype "passive"))
      (node (ref "D102") (pin "1") (pinfunction "A_1") (pintype "passive"))
      (node (ref "D103") (pin "1") (pinfunction "A_1") (pintype "passive"))
      (node (ref "D104") (pin "1") (pinfunction "A_1") (pintype "passive"))
      (node (ref "D105") (pin "1") (pinfunction "A_1") (pintype "passive"))
      (node (ref "D106") (pin "1") (pinfunction "A_1") (pintype "passive"))
      (node (ref "D107") (pin "1") (pinfunction "A_1") (pintype "passive"))
      (node (ref "D108") (pin "1") (pinfunction "A_1") (pintype "passive"))
      (node (ref "D109") (pin "1") (pinfunction "A_1") (pintype "passive"))
      (node (ref "D110") (pin "1") (pinfunction "A_1") (pintype "passive"))
      (node (ref "D111") (pin "1") (pinfunction "A_1") (pintype "passive"))
      (node (ref "D112") (pin "1") (pinfunction "A_1") (pintype "passive"))
      (node (ref "D97") (pin "1") (pinfunction "A_1") (pintype "passive"))
      (node (ref "D98") (pin "1") (pinfunction "A_1") (pintype "passive"))
      (node (ref "D99") (pin "1") (pinfunction "A_1") (pintype "passive"))
    )
    (net (code "10") (name "Net-(D100-K)") (class "Default")
      (node (ref "Catodos1") (pin "4") (pinfunction "4_4") (pintype "passive"))
      (node (ref "D100") (pin "2") (pinfunction "K_2") (pintype "passive"))
      (node (ref "D116") (pin "2") (pinfunction "K_2") (pintype "passive"))
      (node (ref "D132") (pin "2") (pinfunction "K_2") (pintype "passive"))
      (node (ref "D148") (pin "2") (pinfunction "K_2") (pintype "passive"))
      (node (ref "D164") (pin "2") (pinfunction "K_2") (pintype "passive"))
      (node (ref "D180") (pin "2") (pinfunction "K_2") (pintype "passive"))
      (node (ref "D196") (pin "2") (pinfunction "K_2") (pintype "passive"))
      (node (ref "D20") (pin "2") (pinfunction "K_2") (pintype "passive"))
      (node (ref "D212") (pin "2") (pinfunction "K_2") (pintype "passive"))
      (node (ref "D228") (pin "2") (pinfunction "K_2") (pintype "passive"))
      (node (ref "D244") (pin "2") (pinfunction "K_2") (pintype "passive"))
      (node (ref "D36") (pin "2") (pinfunction "K_2") (pintype "passive"))
      (node (ref "D4") (pin "2") (pinfunction "K_2") (pintype "passive"))
      (node (ref "D52") (pin "2") (pinfunction "K_2") (pintype "passive"))
      (node (ref "D68") (pin "2") (pinfunction "K_2") (pintype "passive"))
      (node (ref "D84") (pin "2") (pinfunction "K_2") (pintype "passive"))
    )
    (net (code "11") (name "Net-(D101-K)") (class "Default")
      (node (ref "Catodos1") (pin "5") (pinfunction "5_5") (pintype "passive"))
      (node (ref "D101") (pin "2") (pinfunction "K_2") (pintype "passive"))
      (node (ref "D117") (pin "2") (pinfunction "K_2") (pintype "passive"))
      (node (ref "D133") (pin "2") (pinfunction "K_2") (pintype "passive"))
      (node (ref "D149") (pin "2") (pinfunction "K_2") (pintype "passive"))
      (node (ref "D165") (pin "2") (pinfunction "K_2") (pintype "passive"))
      (node (ref "D181") (pin "2") (pinfunction "K_2") (pintype "passive"))
      (node (ref "D197") (pin "2") (pinfunction "K_2") (pintype "passive"))
      (node (ref "D21") (pin "2") (pinfunction "K_2") (pintype "passive"))
      (node (ref "D213") (pin "2") (pinfunction "K_2") (pintype "passive"))
      (node (ref "D229") (pin "2") (pinfunction "K_2") (pintype "passive"))
      (node (ref "D245") (pin "2") (pinfunction "K_2") (pintype "passive"))
      (node (ref "D37") (pin "2") (pinfunction "K_2") (pintype "passive"))
      (node (ref "D5") (pin "2") (pinfunction "K_2") (pintype "passive"))
      (node (ref "D53") (pin "2") (pinfunction "K_2") (pintype "passive"))
      (node (ref "D69") (pin "2") (pinfunction "K_2") (pintype "passive"))
      (node (ref "D85") (pin "2") (pinfunction "K_2") (pintype "passive"))
    )
    (net (code "12") (name "Net-(D102-K)") (class "Default")
      (node (ref "Catodos1") (pin "6") (pinfunction "6_6") (pintype "passive"))
      (node (ref "D102") (pin "2") (pinfunction "K_2") (pintype "passive"))
      (node (ref "D118") (pin "2") (pinfunction "K_2") (pintype "passive"))
      (node (ref "D134") (pin "2") (pinfunction "K_2") (pintype "passive"))
      (node (ref "D150") (pin "2") (pinfunction "K_2") (pintype "passive"))
      (node (ref "D166") (pin "2") (pinfunction "K_2") (pintype "passive"))
      (node (ref "D182") (pin "2") (pinfunction "K_2") (pintype "passive"))
      (node (ref "D198") (pin "2") (pinfunction "K_2") (pintype "passive"))
      (node (ref "D214") (pin "2") (pinfunction "K_2") (pintype "passive"))
      (node (ref "D22") (pin "2") (pinfunction "K_2") (pintype "passive"))
      (node (ref "D230") (pin "2") (pinfunction "K_2") (pintype "passive"))
      (node (ref "D246") (pin "2") (pinfunction "K_2") (pintype "passive"))
      (node (ref "D38") (pin "2") (pinfunction "K_2") (pintype "passive"))
      (node (ref "D54") (pin "2") (pinfunction "K_2") (pintype "passive"))
      (node (ref "D6") (pin "2") (pinfunction "K_2") (pintype "passive"))
      (node (ref "D70") (pin "2") (pinfunction "K_2") (pintype "passive"))
      (node (ref "D86") (pin "2") (pinfunction "K_2") (pintype "passive"))
    )
    (net (code "13") (name "Net-(D103-K)") (class "Default")
      (node (ref "Catodos1") (pin "7") (pinfunction "7_7") (pintype "passive"))
      (node (ref "D103") (pin "2") (pinfunction "K_2") (pintype "passive"))
      (node (ref "D119") (pin "2") (pinfunction "K_2") (pintype "passive"))
      (node (ref "D135") (pin "2") (pinfunction "K_2") (pintype "passive"))
      (node (ref "D151") (pin "2") (pinfunction "K_2") (pintype "passive"))
      (node (ref "D167") (pin "2") (pinfunction "K_2") (pintype "passive"))
      (node (ref "D183") (pin "2") (pinfunction "K_2") (pintype "passive"))
      (node (ref "D199") (pin "2") (pinfunction "K_2") (pintype "passive"))
      (node (ref "D215") (pin "2") (pinfunction "K_2") (pintype "passive"))
      (node (ref "D23") (pin "2") (pinfunction "K_2") (pintype "passive"))
      (node (ref "D231") (pin "2") (pinfunction "K_2") (pintype "passive"))
      (node (ref "D247") (pin "2") (pinfunction "K_2") (pintype "passive"))
      (node (ref "D39") (pin "2") (pinfunction "K_2") (pintype "passive"))
      (node (ref "D55") (pin "2") (pinfunction "K_2") (pintype "passive"))
      (node (ref "D7") (pin "2") (pinfunction "K_2") (pintype "passive"))
      (node (ref "D71") (pin "2") (pinfunction "K_2") (pintype "passive"))
      (node (ref "D87") (pin "2") (pinfunction "K_2") (pintype "passive"))
    )
    (net (code "14") (name "Net-(D104-K)") (class "Default")
      (node (ref "Catodos1") (pin "8") (pinfunction "8_8") (pintype "passive"))
      (node (ref "D104") (pin "2") (pinfunction "K_2") (pintype "passive"))
      (node (ref "D120") (pin "2") (pinfunction "K_2") (pintype "passive"))
      (node (ref "D136") (pin "2") (pinfunction "K_2") (pintype "passive"))
      (node (ref "D152") (pin "2") (pinfunction "K_2") (pintype "passive"))
      (node (ref "D168") (pin "2") (pinfunction "K_2") (pintype "passive"))
      (node (ref "D184") (pin "2") (pinfunction "K_2") (pintype "passive"))
      (node (ref "D200") (pin "2") (pinfunction "K_2") (pintype "passive"))
      (node (ref "D216") (pin "2") (pinfunction "K_2") (pintype "passive"))
      (node (ref "D232") (pin "2") (pinfunction "K_2") (pintype "passive"))
      (node (ref "D24") (pin "2") (pinfunction "K_2") (pintype "passive"))
      (node (ref "D248") (pin "2") (pinfunction "K_2") (pintype "passive"))
      (node (ref "D40") (pin "2") (pinfunction "K_2") (pintype "passive"))
      (node (ref "D56") (pin "2") (pinfunction "K_2") (pintype "passive"))
      (node (ref "D72") (pin "2") (pinfunction "K_2") (pintype "passive"))
      (node (ref "D8") (pin "2") (pinfunction "K_2") (pintype "passive"))
      (node (ref "D88") (pin "2") (pinfunction "K_2") (pintype "passive"))
    )
    (net (code "15") (name "Net-(D105-K)") (class "Default")
      (node (ref "Catodos1") (pin "9") (pinfunction "9_9") (pintype "passive"))
      (node (ref "D105") (pin "2") (pinfunction "K_2") (pintype "passive"))
      (node (ref "D121") (pin "2") (pinfunction "K_2") (pintype "passive"))
      (node (ref "D137") (pin "2") (pinfunction "K_2") (pintype "passive"))
      (node (ref "D153") (pin "2") (pinfunction "K_2") (pintype "passive"))
      (node (ref "D169") (pin "2") (pinfunction "K_2") (pintype "passive"))
      (node (ref "D185") (pin "2") (pinfunction "K_2") (pintype "passive"))
      (node (ref "D201") (pin "2") (pinfunction "K_2") (pintype "passive"))
      (node (ref "D217") (pin "2") (pinfunction "K_2") (pintype "passive"))
      (node (ref "D233") (pin "2") (pinfunction "K_2") (pintype "passive"))
      (node (ref "D249") (pin "2") (pinfunction "K_2") (pintype "passive"))
      (node (ref "D25") (pin "2") (pinfunction "K_2") (pintype "passive"))
      (node (ref "D41") (pin "2") (pinfunction "K_2") (pintype "passive"))
      (node (ref "D57") (pin "2") (pinfunction "K_2") (pintype "passive"))
      (node (ref "D73") (pin "2") (pinfunction "K_2") (pintype "passive"))
      (node (ref "D89") (pin "2") (pinfunction "K_2") (pintype "passive"))
      (node (ref "D9") (pin "2") (pinfunction "K_2") (pintype "passive"))
    )
    (net (code "16") (name "Net-(D107-K)") (class "Default")
      (node (ref "Catodos1") (pin "11") (pinfunction "11_11") (pintype "passive"))
      (node (ref "D107") (pin "2") (pinfunction "K_2") (pintype "passive"))
      (node (ref "D11") (pin "2") (pinfunction "K_2") (pintype "passive"))
      (node (ref "D123") (pin "2") (pinfunction "K_2") (pintype "passive"))
      (node (ref "D139") (pin "2") (pinfunction "K_2") (pintype "passive"))
      (node (ref "D155") (pin "2") (pinfunction "K_2") (pintype "passive"))
      (node (ref "D171") (pin "2") (pinfunction "K_2") (pintype "passive"))
      (node (ref "D187") (pin "2") (pinfunction "K_2") (pintype "passive"))
      (node (ref "D203") (pin "2") (pinfunction "K_2") (pintype "passive"))
      (node (ref "D219") (pin "2") (pinfunction "K_2") (pintype "passive"))
      (node (ref "D235") (pin "2") (pinfunction "K_2") (pintype "passive"))
      (node (ref "D251") (pin "2") (pinfunction "K_2") (pintype "passive"))
      (node (ref "D27") (pin "2") (pinfunction "K_2") (pintype "passive"))
      (node (ref "D43") (pin "2") (pinfunction "K_2") (pintype "passive"))
      (node (ref "D59") (pin "2") (pinfunction "K_2") (pintype "passive"))
      (node (ref "D75") (pin "2") (pinfunction "K_2") (pintype "passive"))
      (node (ref "D91") (pin "2") (pinfunction "K_2") (pintype "passive"))
    )
    (net (code "17") (name "Net-(D108-K)") (class "Default")
      (node (ref "Catodos1") (pin "12") (pinfunction "12_12") (pintype "passive"))
      (node (ref "D108") (pin "2") (pinfunction "K_2") (pintype "passive"))
      (node (ref "D12") (pin "2") (pinfunction "K_2") (pintype "passive"))
      (node (ref "D124") (pin "2") (pinfunction "K_2") (pintype "passive"))
      (node (ref "D140") (pin "2") (pinfunction "K_2") (pintype "passive"))
      (node (ref "D156") (pin "2") (pinfunction "K_2") (pintype "passive"))
      (node (ref "D172") (pin "2") (pinfunction "K_2") (pintype "passive"))
      (node (ref "D188") (pin "2") (pinfunction "K_2") (pintype "passive"))
      (node (ref "D204") (pin "2") (pinfunction "K_2") (pintype "passive"))
      (node (ref "D220") (pin "2") (pinfunction "K_2") (pintype "passive"))
      (node (ref "D236") (pin "2") (pinfunction "K_2") (pintype "passive"))
      (node (ref "D252") (pin "2") (pinfunction "K_2") (pintype "passive"))
      (node (ref "D28") (pin "2") (pinfunction "K_2") (pintype "passive"))
      (node (ref "D44") (pin "2") (pinfunction "K_2") (pintype "passive"))
      (node (ref "D60") (pin "2") (pinfunction "K_2") (pintype "passive"))
      (node (ref "D76") (pin "2") (pinfunction "K_2") (pintype "passive"))
      (node (ref "D92") (pin "2") (pinfunction "K_2") (pintype "passive"))
    )
    (net (code "18") (name "Net-(D109-K)") (class "Default")
      (node (ref "Catodos1") (pin "13") (pinfunction "13_13") (pintype "passive"))
      (node (ref "D109") (pin "2") (pinfunction "K_2") (pintype "passive"))
      (node (ref "D125") (pin "2") (pinfunction "K_2") (pintype "passive"))
      (node (ref "D13") (pin "2") (pinfunction "K_2") (pintype "passive"))
      (node (ref "D141") (pin "2") (pinfunction "K_2") (pintype "passive"))
      (node (ref "D157") (pin "2") (pinfunction "K_2") (pintype "passive"))
      (node (ref "D173") (pin "2") (pinfunction "K_2") (pintype "passive"))
      (node (ref "D189") (pin "2") (pinfunction "K_2") (pintype "passive"))
      (node (ref "D205") (pin "2") (pinfunction "K_2") (pintype "passive"))
      (node (ref "D221") (pin "2") (pinfunction "K_2") (pintype "passive"))
      (node (ref "D237") (pin "2") (pinfunction "K_2") (pintype "passive"))
      (node (ref "D253") (pin "2") (pinfunction "K_2") (pintype "passive"))
      (node (ref "D29") (pin "2") (pinfunction "K_2") (pintype "passive"))
      (node (ref "D45") (pin "2") (pinfunction "K_2") (pintype "passive"))
      (node (ref "D61") (pin "2") (pinfunction "K_2") (pintype "passive"))
      (node (ref "D77") (pin "2") (pinfunction "K_2") (pintype "passive"))
      (node (ref "D93") (pin "2") (pinfunction "K_2") (pintype "passive"))
    )
    (net (code "19") (name "Net-(D110-K)") (class "Default")
      (node (ref "Catodos1") (pin "14") (pinfunction "14_14") (pintype "passive"))
      (node (ref "D110") (pin "2") (pinfunction "K_2") (pintype "passive"))
      (node (ref "D126") (pin "2") (pinfunction "K_2") (pintype "passive"))
      (node (ref "D14") (pin "2") (pinfunction "K_2") (pintype "passive"))
      (node (ref "D142") (pin "2") (pinfunction "K_2") (pintype "passive"))
      (node (ref "D158") (pin "2") (pinfunction "K_2") (pintype "passive"))
      (node (ref "D174") (pin "2") (pinfunction "K_2") (pintype "passive"))
      (node (ref "D190") (pin "2") (pinfunction "K_2") (pintype "passive"))
      (node (ref "D206") (pin "2") (pinfunction "K_2") (pintype "passive"))
      (node (ref "D222") (pin "2") (pinfunction "K_2") (pintype "passive"))
      (node (ref "D238") (pin "2") (pinfunction "K_2") (pintype "passive"))
      (node (ref "D254") (pin "2") (pinfunction "K_2") (pintype "passive"))
      (node (ref "D30") (pin "2") (pinfunction "K_2") (pintype "passive"))
      (node (ref "D46") (pin "2") (pinfunction "K_2") (pintype "passive"))
      (node (ref "D62") (pin "2") (pinfunction "K_2") (pintype "passive"))
      (node (ref "D78") (pin "2") (pinfunction "K_2") (pintype "passive"))
      (node (ref "D94") (pin "2") (pinfunction "K_2") (pintype "passive"))
    )
    (net (code "20") (name "Net-(D111-K)") (class "Default")
      (node (ref "Catodos1") (pin "15") (pinfunction "15_15") (pintype "passive"))
      (node (ref "D111") (pin "2") (pinfunction "K_2") (pintype "passive"))
      (node (ref "D127") (pin "2") (pinfunction "K_2") (pintype "passive"))
      (node (ref "D143") (pin "2") (pinfunction "K_2") (pintype "passive"))
      (node (ref "D15") (pin "2") (pinfunction "K_2") (pintype "passive"))
      (node (ref "D159") (pin "2") (pinfunction "K_2") (pintype "passive"))
      (node (ref "D175") (pin "2") (pinfunction "K_2") (pintype "passive"))
      (node (ref "D191") (pin "2") (pinfunction "K_2") (pintype "passive"))
      (node (ref "D207") (pin "2") (pinfunction "K_2") (pintype "passive"))
      (node (ref "D223") (pin "2") (pinfunction "K_2") (pintype "passive"))
      (node (ref "D239") (pin "2") (pinfunction "K_2") (pintype "passive"))
      (node (ref "D255") (pin "2") (pinfunction "K_2") (pintype "passive"))
      (node (ref "D31") (pin "2") (pinfunction "K_2") (pintype "passive"))
      (node (ref "D47") (pin "2") (pinfunction "K_2") (pintype "passive"))
      (node (ref "D63") (pin "2") (pinfunction "K_2") (pintype "passive"))
      (node (ref "D79") (pin "2") (pinfunction "K_2") (pintype "passive"))
      (node (ref "D95") (pin "2") (pinfunction "K_2") (pintype "passive"))
    )
    (net (code "21") (name "Net-(D112-K)") (class "Default")
      (node (ref "Catodos1") (pin "16") (pinfunction "16_16") (pintype "passive"))
      (node (ref "D112") (pin "2") (pinfunction "K_2") (pintype "passive"))
      (node (ref "D128") (pin "2") (pinfunction "K_2") (pintype "passive"))
      (node (ref "D144") (pin "2") (pinfunction "K_2") (pintype "passive"))
      (node (ref "D16") (pin "2") (pinfunction "K_2") (pintype "passive"))
      (node (ref "D160") (pin "2") (pinfunction "K_2") (pintype "passive"))
      (node (ref "D176") (pin "2") (pinfunction "K_2") (pintype "passive"))
      (node (ref "D192") (pin "2") (pinfunction "K_2") (pintype "passive"))
      (node (ref "D208") (pin "2") (pinfunction "K_2") (pintype "passive"))
      (node (ref "D224") (pin "2") (pinfunction "K_2") (pintype "passive"))
      (node (ref "D240") (pin "2") (pinfunction "K_2") (pintype "passive"))
      (node (ref "D256") (pin "2") (pinfunction "K_2") (pintype "passive"))
      (node (ref "D32") (pin "2") (pinfunction "K_2") (pintype "passive"))
      (node (ref "D48") (pin "2") (pinfunction "K_2") (pintype "passive"))
      (node (ref "D64") (pin "2") (pinfunction "K_2") (pintype "passive"))
      (node (ref "D80") (pin "2") (pinfunction "K_2") (pintype "passive"))
      (node (ref "D96") (pin "2") (pinfunction "K_2") (pintype "passive"))
    )
    (net (code "22") (name "Net-(D113-A)") (class "Default")
      (node (ref "Anodos1") (pin "8") (pinfunction "8_8") (pintype "passive"))
      (node (ref "Anodos2") (pin "8") (pinfunction "8_8") (pintype "passive"))
      (node (ref "D113") (pin "1") (pinfunction "A_1") (pintype "passive"))
      (node (ref "D114") (pin "1") (pinfunction "A_1") (pintype "passive"))
      (node (ref "D115") (pin "1") (pinfunction "A_1") (pintype "passive"))
      (node (ref "D116") (pin "1") (pinfunction "A_1") (pintype "passive"))
      (node (ref "D117") (pin "1") (pinfunction "A_1") (pintype "passive"))
      (node (ref "D118") (pin "1") (pinfunction "A_1") (pintype "passive"))
      (node (ref "D119") (pin "1") (pinfunction "A_1") (pintype "passive"))
      (node (ref "D120") (pin "1") (pinfunction "A_1") (pintype "passive"))
      (node (ref "D121") (pin "1") (pinfunction "A_1") (pintype "passive"))
      (node (ref "D122") (pin "1") (pinfunction "A_1") (pintype "passive"))
      (node (ref "D123") (pin "1") (pinfunction "A_1") (pintype "passive"))
      (node (ref "D124") (pin "1") (pinfunction "A_1") (pintype "passive"))
      (node (ref "D125") (pin "1") (pinfunction "A_1") (pintype "passive"))
      (node (ref "D126") (pin "1") (pinfunction "A_1") (pintype "passive"))
      (node (ref "D127") (pin "1") (pinfunction "A_1") (pintype "passive"))
      (node (ref "D128") (pin "1") (pinfunction "A_1") (pintype "passive"))
    )
    (net (code "23") (name "Net-(D114-K)") (class "Default")
      (node (ref "Catodos1") (pin "2") (pinfunction "2_2") (pintype "passive"))
      (node (ref "D114") (pin "2") (pinfunction "K_2") (pintype "passive"))
      (node (ref "D130") (pin "2") (pinfunction "K_2") (pintype "passive"))
      (node (ref "D146") (pin "2") (pinfunction "K_2") (pintype "passive"))
      (node (ref "D162") (pin "2") (pinfunction "K_2") (pintype "passive"))
      (node (ref "D178") (pin "2") (pinfunction "K_2") (pintype "passive"))
      (node (ref "D18") (pin "2") (pinfunction "K_2") (pintype "passive"))
      (node (ref "D194") (pin "2") (pinfunction "K_2") (pintype "passive"))
      (node (ref "D2") (pin "2") (pinfunction "K_2") (pintype "passive"))
      (node (ref "D210") (pin "2") (pinfunction "K_2") (pintype "passive"))
      (node (ref "D226") (pin "2") (pinfunction "K_2") (pintype "passive"))
      (node (ref "D242") (pin "2") (pinfunction "K_2") (pintype "passive"))
      (node (ref "D34") (pin "2") (pinfunction "K_2") (pintype "passive"))
      (node (ref "D50") (pin "2") (pinfunction "K_2") (pintype "passive"))
      (node (ref "D66") (pin "2") (pinfunction "K_2") (pintype "passive"))
      (node (ref "D82") (pin "2") (pinfunction "K_2") (pintype "passive"))
      (node (ref "D98") (pin "2") (pinfunction "K_2") (pintype "passive"))
    )
    (net (code "24") (name "Net-(D115-K)") (class "Default")
      (node (ref "Catodos1") (pin "3") (pinfunction "3_3") (pintype "passive"))
      (node (ref "D115") (pin "2") (pinfunction "K_2") (pintype "passive"))
      (node (ref "D131") (pin "2") (pinfunction "K_2") (pintype "passive"))
      (node (ref "D147") (pin "2") (pinfunction "K_2") (pintype "passive"))
      (node (ref "D163") (pin "2") (pinfunction "K_2") (pintype "passive"))
      (node (ref "D179") (pin "2") (pinfunction "K_2") (pintype "passive"))
      (node (ref "D19") (pin "2") (pinfunction "K_2") (pintype "passive"))
      (node (ref "D195") (pin "2") (pinfunction "K_2") (pintype "passive"))
      (node (ref "D211") (pin "2") (pinfunction "K_2") (pintype "passive"))
      (node (ref "D227") (pin "2") (pinfunction "K_2") (pintype "passive"))
      (node (ref "D243") (pin "2") (pinfunction "K_2") (pintype "passive"))
      (node (ref "D3") (pin "2") (pinfunction "K_2") (pintype "passive"))
      (node (ref "D35") (pin "2") (pinfunction "K_2") (pintype "passive"))
      (node (ref "D51") (pin "2") (pinfunction "K_2") (pintype "passive"))
      (node (ref "D67") (pin "2") (pinfunction "K_2") (pintype "passive"))
      (node (ref "D83") (pin "2") (pinfunction "K_2") (pintype "passive"))
      (node (ref "D99") (pin "2") (pinfunction "K_2") (pintype "passive"))
    )
    (net (code "25") (name "Net-(D129-A)") (class "Default")
      (node (ref "Anodos1") (pin "9") (pinfunction "9_9") (pintype "passive"))
      (node (ref "Anodos2") (pin "9") (pinfunction "9_9") (pintype "passive"))
      (node (ref "D129") (pin "1") (pinfunction "A_1") (pintype "passive"))
      (node (ref "D130") (pin "1") (pinfunction "A_1") (pintype "passive"))
      (node (ref "D131") (pin "1") (pinfunction "A_1") (pintype "passive"))
      (node (ref "D132") (pin "1") (pinfunction "A_1") (pintype "passive"))
      (node (ref "D133") (pin "1") (pinfunction "A_1") (pintype "passive"))
      (node (ref "D134") (pin "1") (pinfunction "A_1") (pintype "passive"))
      (node (ref "D135") (pin "1") (pinfunction "A_1") (pintype "passive"))
      (node (ref "D136") (pin "1") (pinfunction "A_1") (pintype "passive"))
      (node (ref "D137") (pin "1") (pinfunction "A_1") (pintype "passive"))
      (node (ref "D138") (pin "1") (pinfunction "A_1") (pintype "passive"))
      (node (ref "D139") (pin "1") (pinfunction "A_1") (pintype "passive"))
      (node (ref "D140") (pin "1") (pinfunction "A_1") (pintype "passive"))
      (node (ref "D141") (pin "1") (pinfunction "A_1") (pintype "passive"))
      (node (ref "D142") (pin "1") (pinfunction "A_1") (pintype "passive"))
      (node (ref "D143") (pin "1") (pinfunction "A_1") (pintype "passive"))
      (node (ref "D144") (pin "1") (pinfunction "A_1") (pintype "passive"))
    )
    (net (code "26") (name "Net-(D145-A)") (class "Default")
      (node (ref "Anodos1") (pin "10") (pinfunction "10_10") (pintype "passive"))
      (node (ref "Anodos2") (pin "10") (pinfunction "10_10") (pintype "passive"))
      (node (ref "D145") (pin "1") (pinfunction "A_1") (pintype "passive"))
      (node (ref "D146") (pin "1") (pinfunction "A_1") (pintype "passive"))
      (node (ref "D147") (pin "1") (pinfunction "A_1") (pintype "passive"))
      (node (ref "D148") (pin "1") (pinfunction "A_1") (pintype "passive"))
      (node (ref "D149") (pin "1") (pinfunction "A_1") (pintype "passive"))
      (node (ref "D150") (pin "1") (pinfunction "A_1") (pintype "passive"))
      (node (ref "D151") (pin "1") (pinfunction "A_1") (pintype "passive"))
      (node (ref "D152") (pin "1") (pinfunction "A_1") (pintype "passive"))
      (node (ref "D153") (pin "1") (pinfunction "A_1") (pintype "passive"))
      (node (ref "D154") (pin "1") (pinfunction "A_1") (pintype "passive"))
      (node (ref "D155") (pin "1") (pinfunction "A_1") (pintype "passive"))
      (node (ref "D156") (pin "1") (pinfunction "A_1") (pintype "passive"))
      (node (ref "D157") (pin "1") (pinfunction "A_1") (pintype "passive"))
      (node (ref "D158") (pin "1") (pinfunction "A_1") (pintype "passive"))
      (node (ref "D159") (pin "1") (pinfunction "A_1") (pintype "passive"))
      (node (ref "D160") (pin "1") (pinfunction "A_1") (pintype "passive"))
    )
    (net (code "27") (name "Net-(D161-A)") (class "Default")
      (node (ref "Anodos1") (pin "11") (pinfunction "11_11") (pintype "passive"))
      (node (ref "Anodos2") (pin "11") (pinfunction "11_11") (pintype "passive"))
      (node (ref "D161") (pin "1") (pinfunction "A_1") (pintype "passive"))
      (node (ref "D162") (pin "1") (pinfunction "A_1") (pintype "passive"))
      (node (ref "D163") (pin "1") (pinfunction "A_1") (pintype "passive"))
      (node (ref "D164") (pin "1") (pinfunction "A_1") (pintype "passive"))
      (node (ref "D165") (pin "1") (pinfunction "A_1") (pintype "passive"))
      (node (ref "D166") (pin "1") (pinfunction "A_1") (pintype "passive"))
      (node (ref "D167") (pin "1") (pinfunction "A_1") (pintype "passive"))
      (node (ref "D168") (pin "1") (pinfunction "A_1") (pintype "passive"))
      (node (ref "D169") (pin "1") (pinfunction "A_1") (pintype "passive"))
      (node (ref "D170") (pin "1") (pinfunction "A_1") (pintype "passive"))
      (node (ref "D171") (pin "1") (pinfunction "A_1") (pintype "passive"))
      (node (ref "D172") (pin "1") (pinfunction "A_1") (pintype "passive"))
      (node (ref "D173") (pin "1") (pinfunction "A_1") (pintype "passive"))
      (node (ref "D174") (pin "1") (pinfunction "A_1") (pintype "passive"))
      (node (ref "D175") (pin "1") (pinfunction "A_1") (pintype "passive"))
      (node (ref "D176") (pin "1") (pinfunction "A_1") (pintype "passive"))
    )
    (net (code "28") (name "Net-(D177-A)") (class "Default")
      (node (ref "Anodos1") (pin "12") (pinfunction "12_12") (pintype "passive"))
      (node (ref "Anodos2") (pin "12") (pinfunction "12_12") (pintype "passive"))
      (node (ref "D177") (pin "1") (pinfunction "A_1") (pintype "passive"))
      (node (ref "D178") (pin "1") (pinfunction "A_1") (pintype "passive"))
      (node (ref "D179") (pin "1") (pinfunction "A_1") (pintype "passive"))
      (node (ref "D180") (pin "1") (pinfunction "A_1") (pintype "passive"))
      (node (ref "D181") (pin "1") (pinfunction "A_1") (pintype "passive"))
      (node (ref "D182") (pin "1") (pinfunction "A_1") (pintype "passive"))
      (node (ref "D183") (pin "1") (pinfunction "A_1") (pintype "passive"))
      (node (ref "D184") (pin "1") (pinfunction "A_1") (pintype "passive"))
      (node (ref "D185") (pin "1") (pinfunction "A_1") (pintype "passive"))
      (node (ref "D186") (pin "1") (pinfunction "A_1") (pintype "passive"))
      (node (ref "D187") (pin "1") (pinfunction "A_1") (pintype "passive"))
      (node (ref "D188") (pin "1") (pinfunction "A_1") (pintype "passive"))
      (node (ref "D189") (pin "1") (pinfunction "A_1") (pintype "passive"))
      (node (ref "D190") (pin "1") (pinfunction "A_1") (pintype "passive"))
      (node (ref "D191") (pin "1") (pinfunction "A_1") (pintype "passive"))
      (node (ref "D192") (pin "1") (pinfunction "A_1") (pintype "passive"))
    )
    (net (code "29") (name "Net-(D193-A)") (class "Default")
      (node (ref "Anodos1") (pin "13") (pinfunction "13_13") (pintype "passive"))
      (node (ref "Anodos2") (pin "13") (pinfunction "13_13") (pintype "passive"))
      (node (ref "D193") (pin "1") (pinfunction "A_1") (pintype "passive"))
      (node (ref "D194") (pin "1") (pinfunction "A_1") (pintype "passive"))
      (node (ref "D195") (pin "1") (pinfunction "A_1") (pintype "passive"))
      (node (ref "D196") (pin "1") (pinfunction "A_1") (pintype "passive"))
      (node (ref "D197") (pin "1") (pinfunction "A_1") (pintype "passive"))
      (node (ref "D198") (pin "1") (pinfunction "A_1") (pintype "passive"))
      (node (ref "D199") (pin "1") (pinfunction "A_1") (pintype "passive"))
      (node (ref "D200") (pin "1") (pinfunction "A_1") (pintype "passive"))
      (node (ref "D201") (pin "1") (pinfunction "A_1") (pintype "passive"))
      (node (ref "D202") (pin "1") (pinfunction "A_1") (pintype "passive"))
      (node (ref "D203") (pin "1") (pinfunction "A_1") (pintype "passive"))
      (node (ref "D204") (pin "1") (pinfunction "A_1") (pintype "passive"))
      (node (ref "D205") (pin "1") (pinfunction "A_1") (pintype "passive"))
      (node (ref "D206") (pin "1") (pinfunction "A_1") (pintype "passive"))
      (node (ref "D207") (pin "1") (pinfunction "A_1") (pintype "passive"))
      (node (ref "D208") (pin "1") (pinfunction "A_1") (pintype "passive"))
    )
    (net (code "30") (name "Net-(D209-A)") (class "Default")
      (node (ref "Anodos1") (pin "14") (pinfunction "14_14") (pintype "passive"))
      (node (ref "Anodos2") (pin "14") (pinfunction "14_14") (pintype "passive"))
      (node (ref "D209") (pin "1") (pinfunction "A_1") (pintype "passive"))
      (node (ref "D210") (pin "1") (pinfunction "A_1") (pintype "passive"))
      (node (ref "D211") (pin "1") (pinfunction "A_1") (pintype "passive"))
      (node (ref "D212") (pin "1") (pinfunction "A_1") (pintype "passive"))
      (node (ref "D213") (pin "1") (pinfunction "A_1") (pintype "passive"))
      (node (ref "D214") (pin "1") (pinfunction "A_1") (pintype "passive"))
      (node (ref "D215") (pin "1") (pinfunction "A_1") (pintype "passive"))
      (node (ref "D216") (pin "1") (pinfunction "A_1") (pintype "passive"))
      (node (ref "D217") (pin "1") (pinfunction "A_1") (pintype "passive"))
      (node (ref "D218") (pin "1") (pinfunction "A_1") (pintype "passive"))
      (node (ref "D219") (pin "1") (pinfunction "A_1") (pintype "passive"))
      (node (ref "D220") (pin "1") (pinfunction "A_1") (pintype "passive"))
      (node (ref "D221") (pin "1") (pinfunction "A_1") (pintype "passive"))
      (node (ref "D222") (pin "1") (pinfunction "A_1") (pintype "passive"))
      (node (ref "D223") (pin "1") (pinfunction "A_1") (pintype "passive"))
      (node (ref "D224") (pin "1") (pinfunction "A_1") (pintype "passive"))
    )
    (net (code "31") (name "Net-(D225-A)") (class "Default")
      (node (ref "Anodos1") (pin "15") (pinfunction "15_15") (pintype "passive"))
      (node (ref "Anodos2") (pin "15") (pinfunction "15_15") (pintype "passive"))
      (node (ref "D225") (pin "1") (pinfunction "A_1") (pintype "passive"))
      (node (ref "D226") (pin "1") (pinfunction "A_1") (pintype "passive"))
      (node (ref "D227") (pin "1") (pinfunction "A_1") (pintype "passive"))
      (node (ref "D228") (pin "1") (pinfunction "A_1") (pintype "passive"))
      (node (ref "D229") (pin "1") (pinfunction "A_1") (pintype "passive"))
      (node (ref "D230") (pin "1") (pinfunction "A_1") (pintype "passive"))
      (node (ref "D231") (pin "1") (pinfunction "A_1") (pintype "passive"))
      (node (ref "D232") (pin "1") (pinfunction "A_1") (pintype "passive"))
      (node (ref "D233") (pin "1") (pinfunction "A_1") (pintype "passive"))
      (node (ref "D234") (pin "1") (pinfunction "A_1") (pintype "passive"))
      (node (ref "D235") (pin "1") (pinfunction "A_1") (pintype "passive"))
      (node (ref "D236") (pin "1") (pinfunction "A_1") (pintype "passive"))
      (node (ref "D237") (pin "1") (pinfunction "A_1") (pintype "passive"))
      (node (ref "D238") (pin "1") (pinfunction "A_1") (pintype "passive"))
      (node (ref "D239") (pin "1") (pinfunction "A_1") (pintype "passive"))
      (node (ref "D240") (pin "1") (pinfunction "A_1") (pintype "passive"))
    )
    (net (code "32") (name "Net-(D241-A)") (class "Default")
      (node (ref "Anodos1") (pin "16") (pinfunction "16_16") (pintype "passive"))
      (node (ref "Anodos2") (pin "16") (pinfunction "16_16") (pintype "passive"))
      (node (ref "D241") (pin "1") (pinfunction "A_1") (pintype "passive"))
      (node (ref "D242") (pin "1") (pinfunction "A_1") (pintype "passive"))
      (node (ref "D243") (pin "1") (pinfunction "A_1") (pintype "passive"))
      (node (ref "D244") (pin "1") (pinfunction "A_1") (pintype "passive"))
      (node (ref "D245") (pin "1") (pinfunction "A_1") (pintype "passive"))
      (node (ref "D246") (pin "1") (pinfunction "A_1") (pintype "passive"))
      (node (ref "D247") (pin "1") (pinfunction "A_1") (pintype "passive"))
      (node (ref "D248") (pin "1") (pinfunction "A_1") (pintype "passive"))
      (node (ref "D249") (pin "1") (pinfunction "A_1") (pintype "passive"))
      (node (ref "D250") (pin "1") (pinfunction "A_1") (pintype "passive"))
      (node (ref "D251") (pin "1") (pinfunction "A_1") (pintype "passive"))
      (node (ref "D252") (pin "1") (pinfunction "A_1") (pintype "passive"))
      (node (ref "D253") (pin "1") (pinfunction "A_1") (pintype "passive"))
      (node (ref "D254") (pin "1") (pinfunction "A_1") (pintype "passive"))
      (node (ref "D255") (pin "1") (pinfunction "A_1") (pintype "passive"))
      (node (ref "D256") (pin "1") (pinfunction "A_1") (pintype "passive"))
    )
  )
)
